# AtoVproject_16n_V1_1.net
KiCad netlist of a schematic drawn in EAGLE
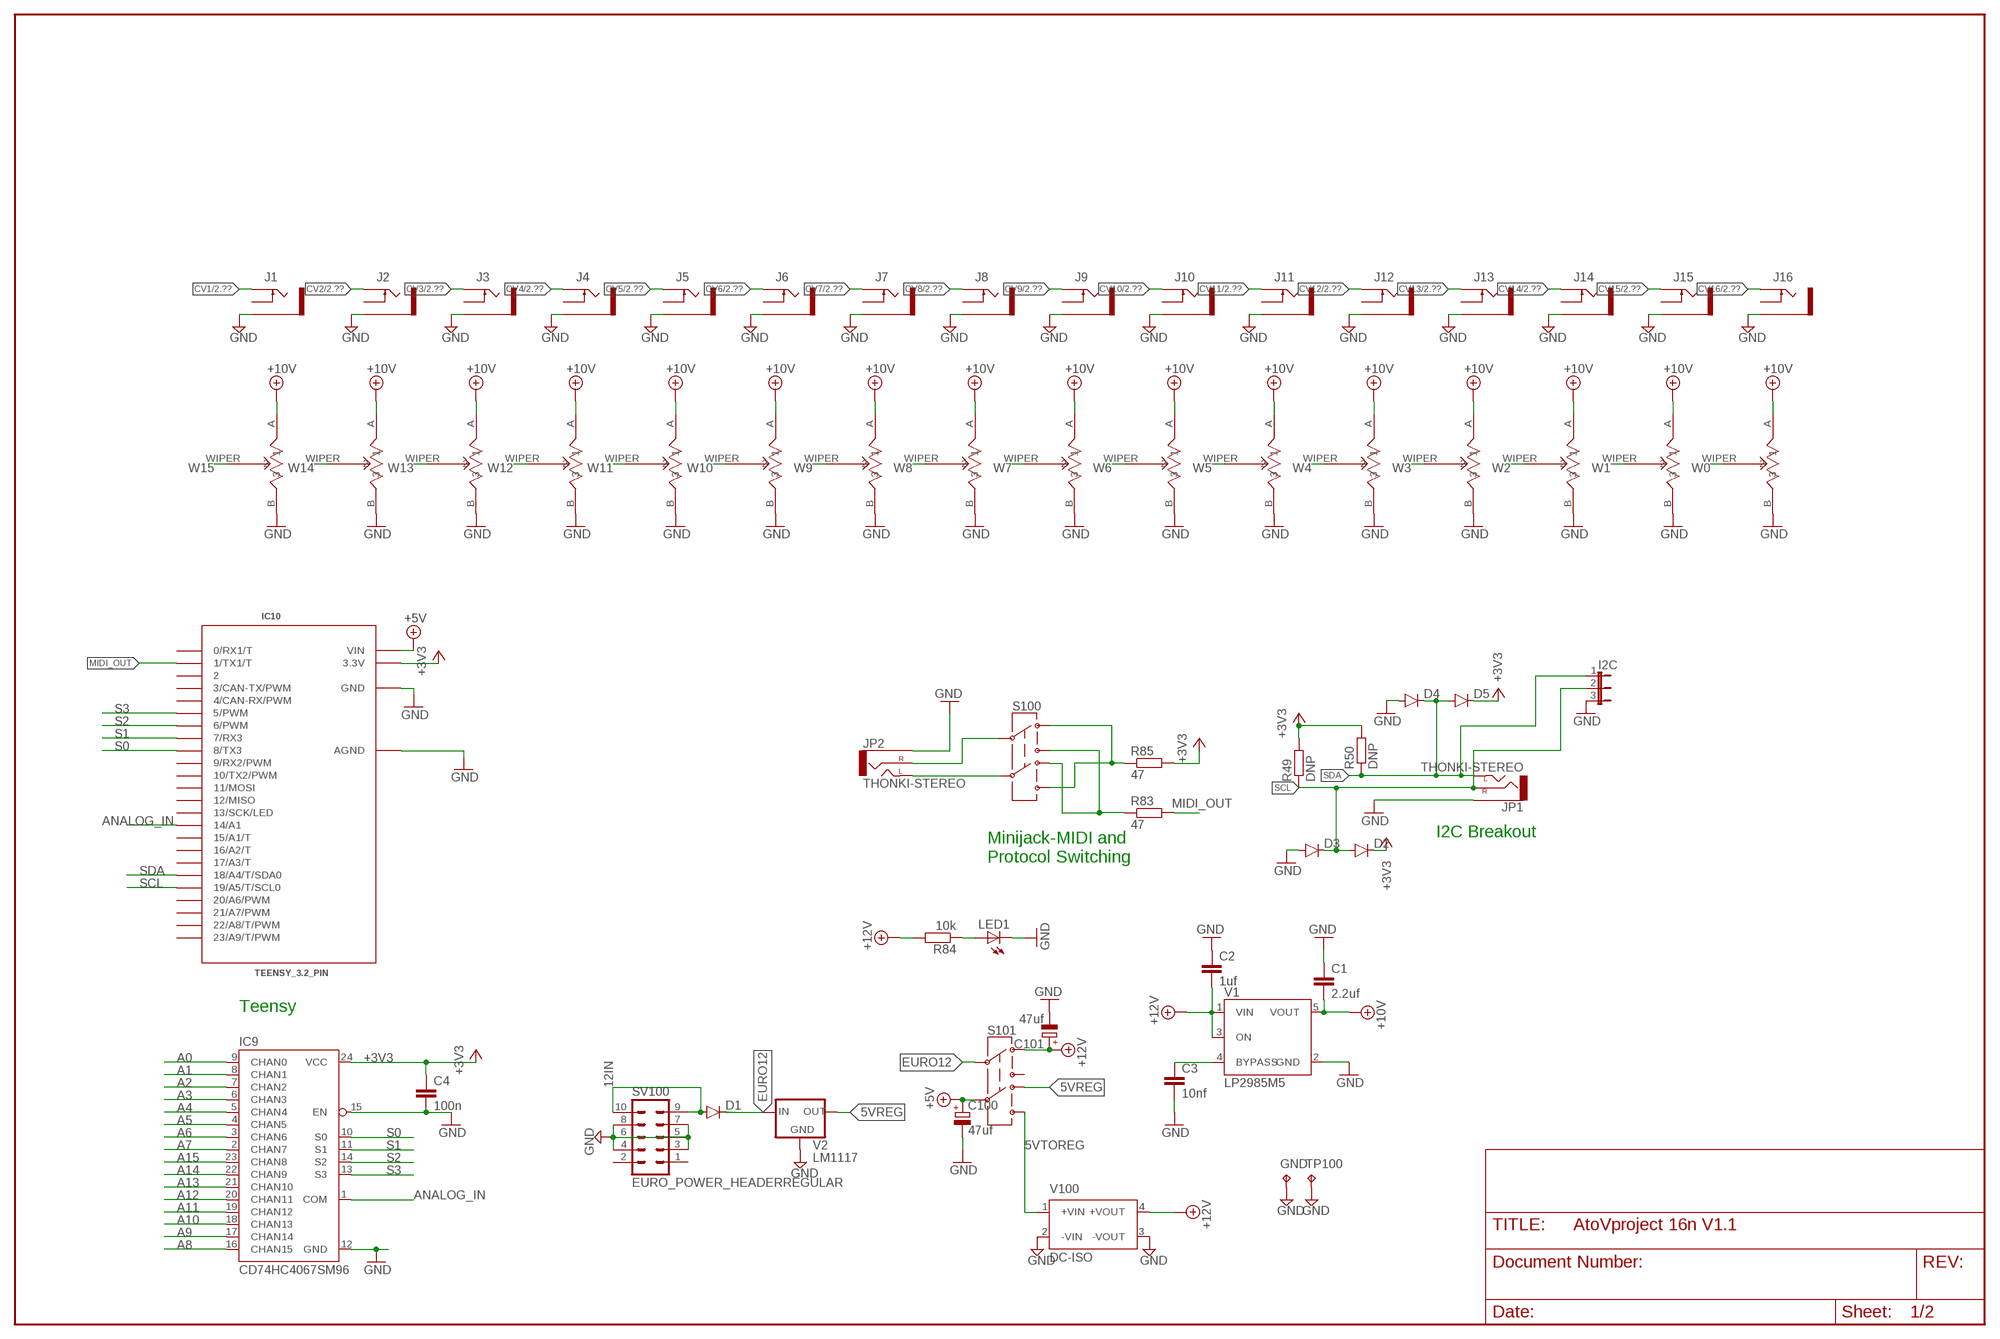
[diagram p0: schematic, sheet 1]
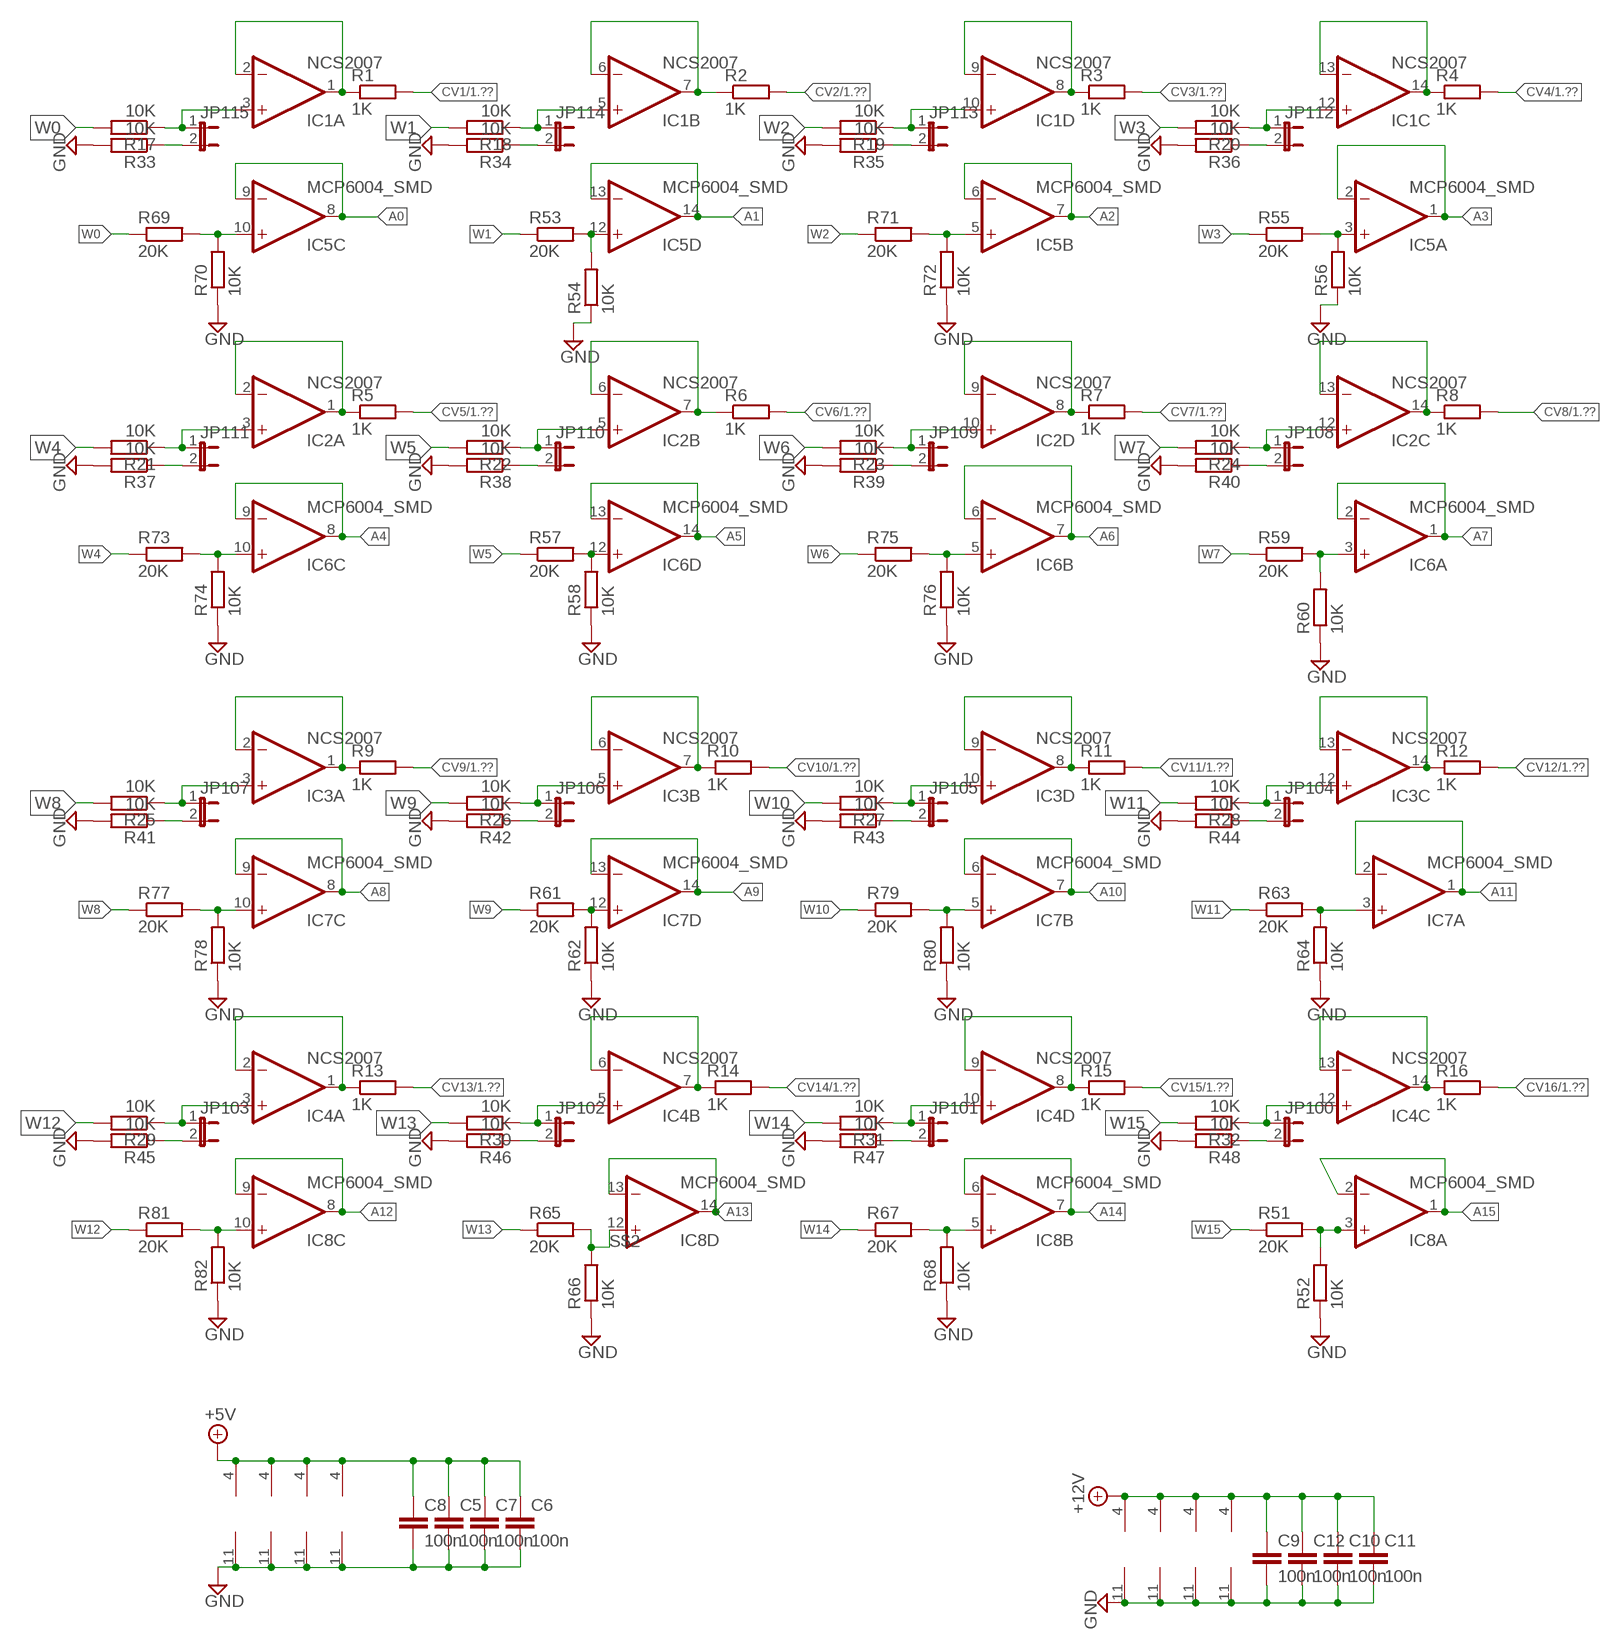
[diagram p1: schematic, sheet 2]

(export (version "E")
  (design (tool "Eeschema 10.0.6"))
  (components
    (comp (ref "C5")
      (value "100n")
      (footprint "eagle-import:C0805")
      (libsource (lib "eagle-import") (part "C-EUC0805"))
    )
    (comp (ref "C6")
      (value "100n")
      (footprint "eagle-import:C0805")
      (libsource (lib "eagle-import") (part "C-EUC0805"))
    )
    (comp (ref "C7")
      (value "100n")
      (footprint "eagle-import:C0805")
      (libsource (lib "eagle-import") (part "C-EUC0805"))
    )
    (comp (ref "C8")
      (value "100n")
      (footprint "eagle-import:C0805")
      (libsource (lib "eagle-import") (part "C-EUC0805"))
    )
    (comp (ref "C9")
      (value "100n")
      (footprint "eagle-import:C0805")
      (libsource (lib "eagle-import") (part "C-EUC0805"))
    )
    (comp (ref "C10")
      (value "100n")
      (footprint "eagle-import:C0805")
      (libsource (lib "eagle-import") (part "C-EUC0805"))
    )
    (comp (ref "C11")
      (value "100n")
      (footprint "eagle-import:C0805")
      (libsource (lib "eagle-import") (part "C-EUC0805"))
    )
    (comp (ref "C12")
      (value "100n")
      (footprint "eagle-import:C0805")
      (libsource (lib "eagle-import") (part "C-EUC0805"))
    )
    (comp (ref "IC1")
      (value "NCS2007")
      (footprint "eagle-import:SO14")
      (libsource (lib "eagle-import") (part "TL074"))
    )
    (comp (ref "IC2")
      (value "NCS2007")
      (footprint "eagle-import:SO14")
      (libsource (lib "eagle-import") (part "TL074"))
    )
    (comp (ref "IC3")
      (value "NCS2007")
      (footprint "eagle-import:SO14")
      (libsource (lib "eagle-import") (part "TL074"))
    )
    (comp (ref "IC4")
      (value "NCS2007")
      (footprint "eagle-import:SO14")
      (libsource (lib "eagle-import") (part "TL074"))
    )
    (comp (ref "IC5")
      (value "MCP6004_SMD")
      (footprint "eagle-import:SO14")
      (libsource (lib "eagle-import") (part "MCP6004_SMD"))
    )
    (comp (ref "IC6")
      (value "MCP6004_SMD")
      (footprint "eagle-import:SO14")
      (libsource (lib "eagle-import") (part "MCP6004_SMD"))
    )
    (comp (ref "IC7")
      (value "MCP6004_SMD")
      (footprint "eagle-import:SO14")
      (libsource (lib "eagle-import") (part "MCP6004_SMD"))
    )
    (comp (ref "IC8")
      (value "MCP6004_SMD")
      (footprint "eagle-import:SO14")
      (libsource (lib "eagle-import") (part "MCP6004_SMD"))
    )
    (comp (ref "JP100")
      (value "JP1E3D")
      (footprint "eagle-import:1X02")
      (libsource (lib "eagle-import") (part "JP1E3D"))
    )
    (comp (ref "JP101")
      (value "JP1E3D")
      (footprint "eagle-import:1X02")
      (libsource (lib "eagle-import") (part "JP1E3D"))
    )
    (comp (ref "JP102")
      (value "JP1E3D")
      (footprint "eagle-import:1X02")
      (libsource (lib "eagle-import") (part "JP1E3D"))
    )
    (comp (ref "JP103")
      (value "JP1E3D")
      (footprint "eagle-import:1X02")
      (libsource (lib "eagle-import") (part "JP1E3D"))
    )
    (comp (ref "JP104")
      (value "JP1E3D")
      (footprint "eagle-import:1X02")
      (libsource (lib "eagle-import") (part "JP1E3D"))
    )
    (comp (ref "JP105")
      (value "JP1E3D")
      (footprint "eagle-import:1X02")
      (libsource (lib "eagle-import") (part "JP1E3D"))
    )
    (comp (ref "JP106")
      (value "JP1E3D")
      (footprint "eagle-import:1X02")
      (libsource (lib "eagle-import") (part "JP1E3D"))
    )
    (comp (ref "JP107")
      (value "JP1E3D")
      (footprint "eagle-import:1X02")
      (libsource (lib "eagle-import") (part "JP1E3D"))
    )
    (comp (ref "JP108")
      (value "JP1E3D")
      (footprint "eagle-import:1X02")
      (libsource (lib "eagle-import") (part "JP1E3D"))
    )
    (comp (ref "JP109")
      (value "JP1E3D")
      (footprint "eagle-import:1X02")
      (libsource (lib "eagle-import") (part "JP1E3D"))
    )
    (comp (ref "JP110")
      (value "JP1E3D")
      (footprint "eagle-import:1X02")
      (libsource (lib "eagle-import") (part "JP1E3D"))
    )
    (comp (ref "JP111")
      (value "JP1E3D")
      (footprint "eagle-import:1X02")
      (libsource (lib "eagle-import") (part "JP1E3D"))
    )
    (comp (ref "JP112")
      (value "JP1E3D")
      (footprint "eagle-import:1X02")
      (libsource (lib "eagle-import") (part "JP1E3D"))
    )
    (comp (ref "JP113")
      (value "JP1E3D")
      (footprint "eagle-import:1X02")
      (libsource (lib "eagle-import") (part "JP1E3D"))
    )
    (comp (ref "JP114")
      (value "JP1E3D")
      (footprint "eagle-import:1X02")
      (libsource (lib "eagle-import") (part "JP1E3D"))
    )
    (comp (ref "JP115")
      (value "JP1E3D")
      (footprint "eagle-import:1X02")
      (libsource (lib "eagle-import") (part "JP1E3D"))
    )
    (comp (ref "R1")
      (value "1K")
      (footprint "eagle-import:R0805")
      (libsource (lib "eagle-import") (part "R-EU_R0805"))
    )
    (comp (ref "R2")
      (value "1K")
      (footprint "eagle-import:R0805")
      (libsource (lib "eagle-import") (part "R-EU_R0805"))
    )
    (comp (ref "R3")
      (value "1K")
      (footprint "eagle-import:R0805")
      (libsource (lib "eagle-import") (part "R-EU_R0805"))
    )
    (comp (ref "R4")
      (value "1K")
      (footprint "eagle-import:R0805")
      (libsource (lib "eagle-import") (part "R-EU_R0805"))
    )
    (comp (ref "R5")
      (value "1K")
      (footprint "eagle-import:R0805")
      (libsource (lib "eagle-import") (part "R-EU_R0805"))
    )
    (comp (ref "R6")
      (value "1K")
      (footprint "eagle-import:R0805")
      (libsource (lib "eagle-import") (part "R-EU_R0805"))
    )
    (comp (ref "R7")
      (value "1K")
      (footprint "eagle-import:R0805")
      (libsource (lib "eagle-import") (part "R-EU_R0805"))
    )
    (comp (ref "R8")
      (value "1K")
      (footprint "eagle-import:R0805")
      (libsource (lib "eagle-import") (part "R-EU_R0805"))
    )
    (comp (ref "R9")
      (value "1K")
      (footprint "eagle-import:R0805")
      (libsource (lib "eagle-import") (part "R-EU_R0805"))
    )
    (comp (ref "R10")
      (value "1K")
      (footprint "eagle-import:R0805")
      (libsource (lib "eagle-import") (part "R-EU_R0805"))
    )
    (comp (ref "R11")
      (value "1K")
      (footprint "eagle-import:R0805")
      (libsource (lib "eagle-import") (part "R-EU_R0805"))
    )
    (comp (ref "R12")
      (value "1K")
      (footprint "eagle-import:R0805")
      (libsource (lib "eagle-import") (part "R-EU_R0805"))
    )
    (comp (ref "R13")
      (value "1K")
      (footprint "eagle-import:R0805")
      (libsource (lib "eagle-import") (part "R-EU_R0805"))
    )
    (comp (ref "R14")
      (value "1K")
      (footprint "eagle-import:R0805")
      (libsource (lib "eagle-import") (part "R-EU_R0805"))
    )
    (comp (ref "R15")
      (value "1K")
      (footprint "eagle-import:R0805")
      (libsource (lib "eagle-import") (part "R-EU_R0805"))
    )
    (comp (ref "R16")
      (value "1K")
      (footprint "eagle-import:R0805")
      (libsource (lib "eagle-import") (part "R-EU_R0805"))
    )
    (comp (ref "R17")
      (value "10K")
      (footprint "eagle-import:R0805")
      (libsource (lib "eagle-import") (part "R-EU_R0805"))
    )
    (comp (ref "R18")
      (value "10K")
      (footprint "eagle-import:R0805")
      (libsource (lib "eagle-import") (part "R-EU_R0805"))
    )
    (comp (ref "R19")
      (value "10K")
      (footprint "eagle-import:R0805")
      (libsource (lib "eagle-import") (part "R-EU_R0805"))
    )
    (comp (ref "R20")
      (value "10K")
      (footprint "eagle-import:R0805")
      (libsource (lib "eagle-import") (part "R-EU_R0805"))
    )
    (comp (ref "R21")
      (value "10K")
      (footprint "eagle-import:R0805")
      (libsource (lib "eagle-import") (part "R-EU_R0805"))
    )
    (comp (ref "R22")
      (value "10K")
      (footprint "eagle-import:R0805")
      (libsource (lib "eagle-import") (part "R-EU_R0805"))
    )
    (comp (ref "R23")
      (value "10K")
      (footprint "eagle-import:R0805")
      (libsource (lib "eagle-import") (part "R-EU_R0805"))
    )
    (comp (ref "R24")
      (value "10K")
      (footprint "eagle-import:R0805")
      (libsource (lib "eagle-import") (part "R-EU_R0805"))
    )
    (comp (ref "R25")
      (value "10K")
      (footprint "eagle-import:R0805")
      (libsource (lib "eagle-import") (part "R-EU_R0805"))
    )
    (comp (ref "R26")
      (value "10K")
      (footprint "eagle-import:R0805")
      (libsource (lib "eagle-import") (part "R-EU_R0805"))
    )
    (comp (ref "R27")
      (value "10K")
      (footprint "eagle-import:R0805")
      (libsource (lib "eagle-import") (part "R-EU_R0805"))
    )
    (comp (ref "R28")
      (value "10K")
      (footprint "eagle-import:R0805")
      (libsource (lib "eagle-import") (part "R-EU_R0805"))
    )
    (comp (ref "R29")
      (value "10K")
      (footprint "eagle-import:R0805")
      (libsource (lib "eagle-import") (part "R-EU_R0805"))
    )
    (comp (ref "R30")
      (value "10K")
      (footprint "eagle-import:R0805")
      (libsource (lib "eagle-import") (part "R-EU_R0805"))
    )
    (comp (ref "R31")
      (value "10K")
      (footprint "eagle-import:R0805")
      (libsource (lib "eagle-import") (part "R-EU_R0805"))
    )
    (comp (ref "R32")
      (value "10K")
      (footprint "eagle-import:R0805")
      (libsource (lib "eagle-import") (part "R-EU_R0805"))
    )
    (comp (ref "R33")
      (value "10K")
      (footprint "eagle-import:R0805")
      (libsource (lib "eagle-import") (part "R-EU_R0805"))
    )
    (comp (ref "R34")
      (value "10K")
      (footprint "eagle-import:R0805")
      (libsource (lib "eagle-import") (part "R-EU_R0805"))
    )
    (comp (ref "R35")
      (value "10K")
      (footprint "eagle-import:R0805")
      (libsource (lib "eagle-import") (part "R-EU_R0805"))
    )
    (comp (ref "R36")
      (value "10K")
      (footprint "eagle-import:R0805")
      (libsource (lib "eagle-import") (part "R-EU_R0805"))
    )
    (comp (ref "R37")
      (value "10K")
      (footprint "eagle-import:R0805")
      (libsource (lib "eagle-import") (part "R-EU_R0805"))
    )
    (comp (ref "R38")
      (value "10K")
      (footprint "eagle-import:R0805")
      (libsource (lib "eagle-import") (part "R-EU_R0805"))
    )
    (comp (ref "R39")
      (value "10K")
      (footprint "eagle-import:R0805")
      (libsource (lib "eagle-import") (part "R-EU_R0805"))
    )
    (comp (ref "R40")
      (value "10K")
      (footprint "eagle-import:R0805")
      (libsource (lib "eagle-import") (part "R-EU_R0805"))
    )
    (comp (ref "R41")
      (value "10K")
      (footprint "eagle-import:R0805")
      (libsource (lib "eagle-import") (part "R-EU_R0805"))
    )
    (comp (ref "R42")
      (value "10K")
      (footprint "eagle-import:R0805")
      (libsource (lib "eagle-import") (part "R-EU_R0805"))
    )
    (comp (ref "R43")
      (value "10K")
      (footprint "eagle-import:R0805")
      (libsource (lib "eagle-import") (part "R-EU_R0805"))
    )
    (comp (ref "R44")
      (value "10K")
      (footprint "eagle-import:R0805")
      (libsource (lib "eagle-import") (part "R-EU_R0805"))
    )
    (comp (ref "R45")
      (value "10K")
      (footprint "eagle-import:R0805")
      (libsource (lib "eagle-import") (part "R-EU_R0805"))
    )
    (comp (ref "R46")
      (value "10K")
      (footprint "eagle-import:R0805")
      (libsource (lib "eagle-import") (part "R-EU_R0805"))
    )
    (comp (ref "R47")
      (value "10K")
      (footprint "eagle-import:R0805")
      (libsource (lib "eagle-import") (part "R-EU_R0805"))
    )
    (comp (ref "R48")
      (value "10K")
      (footprint "eagle-import:R0805")
      (libsource (lib "eagle-import") (part "R-EU_R0805"))
    )
    (comp (ref "R51")
      (value "20K")
      (footprint "eagle-import:R0805")
      (libsource (lib "eagle-import") (part "R-EU_R0805"))
    )
    (comp (ref "R52")
      (value "10K")
      (footprint "eagle-import:R0805")
      (libsource (lib "eagle-import") (part "R-EU_R0805"))
    )
    (comp (ref "R53")
      (value "20K")
      (footprint "eagle-import:R0805")
      (libsource (lib "eagle-import") (part "R-EU_R0805"))
    )
    (comp (ref "R54")
      (value "10K")
      (footprint "eagle-import:R0805")
      (libsource (lib "eagle-import") (part "R-EU_R0805"))
    )
    (comp (ref "R55")
      (value "20K")
      (footprint "eagle-import:R0805")
      (libsource (lib "eagle-import") (part "R-EU_R0805"))
    )
    (comp (ref "R56")
      (value "10K")
      (footprint "eagle-import:R0805")
      (libsource (lib "eagle-import") (part "R-EU_R0805"))
    )
    (comp (ref "R57")
      (value "20K")
      (footprint "eagle-import:R0805")
      (libsource (lib "eagle-import") (part "R-EU_R0805"))
    )
    (comp (ref "R58")
      (value "10K")
      (footprint "eagle-import:R0805")
      (libsource (lib "eagle-import") (part "R-EU_R0805"))
    )
    (comp (ref "R59")
      (value "20K")
      (footprint "eagle-import:R0805")
      (libsource (lib "eagle-import") (part "R-EU_R0805"))
    )
    (comp (ref "R60")
      (value "10K")
      (footprint "eagle-import:R0805")
      (libsource (lib "eagle-import") (part "R-EU_R0805"))
    )
    (comp (ref "R61")
      (value "20K")
      (footprint "eagle-import:R0805")
      (libsource (lib "eagle-import") (part "R-EU_R0805"))
    )
    (comp (ref "R62")
      (value "10K")
      (footprint "eagle-import:R0805")
      (libsource (lib "eagle-import") (part "R-EU_R0805"))
    )
    (comp (ref "R63")
      (value "20K")
      (footprint "eagle-import:R0805")
      (libsource (lib "eagle-import") (part "R-EU_R0805"))
    )
    (comp (ref "R64")
      (value "10K")
      (footprint "eagle-import:R0805")
      (libsource (lib "eagle-import") (part "R-EU_R0805"))
    )
    (comp (ref "R65")
      (value "20K")
      (footprint "eagle-import:R0805")
      (libsource (lib "eagle-import") (part "R-EU_R0805"))
    )
    (comp (ref "R66")
      (value "10K")
      (footprint "eagle-import:R0805")
      (libsource (lib "eagle-import") (part "R-EU_R0805"))
    )
    (comp (ref "R67")
      (value "20K")
      (footprint "eagle-import:R0805")
      (libsource (lib "eagle-import") (part "R-EU_R0805"))
    )
    (comp (ref "R68")
      (value "10K")
      (footprint "eagle-import:R0805")
      (libsource (lib "eagle-import") (part "R-EU_R0805"))
    )
    (comp (ref "R69")
      (value "20K")
      (footprint "eagle-import:R0805")
      (libsource (lib "eagle-import") (part "R-EU_R0805"))
    )
    (comp (ref "R70")
      (value "10K")
      (footprint "eagle-import:R0805")
      (libsource (lib "eagle-import") (part "R-EU_R0805"))
    )
    (comp (ref "R71")
      (value "20K")
      (footprint "eagle-import:R0805")
      (libsource (lib "eagle-import") (part "R-EU_R0805"))
    )
    (comp (ref "R72")
      (value "10K")
      (footprint "eagle-import:R0805")
      (libsource (lib "eagle-import") (part "R-EU_R0805"))
    )
    (comp (ref "R73")
      (value "20K")
      (footprint "eagle-import:R0805")
      (libsource (lib "eagle-import") (part "R-EU_R0805"))
    )
    (comp (ref "R74")
      (value "10K")
      (footprint "eagle-import:R0805")
      (libsource (lib "eagle-import") (part "R-EU_R0805"))
    )
    (comp (ref "R75")
      (value "20K")
      (footprint "eagle-import:R0805")
      (libsource (lib "eagle-import") (part "R-EU_R0805"))
    )
    (comp (ref "R76")
      (value "10K")
      (footprint "eagle-import:R0805")
      (libsource (lib "eagle-import") (part "R-EU_R0805"))
    )
    (comp (ref "R77")
      (value "20K")
      (footprint "eagle-import:R0805")
      (libsource (lib "eagle-import") (part "R-EU_R0805"))
    )
    (comp (ref "R78")
      (value "10K")
      (footprint "eagle-import:R0805")
      (libsource (lib "eagle-import") (part "R-EU_R0805"))
    )
    (comp (ref "R79")
      (value "20K")
      (footprint "eagle-import:R0805")
      (libsource (lib "eagle-import") (part "R-EU_R0805"))
    )
    (comp (ref "R80")
      (value "10K")
      (footprint "eagle-import:R0805")
      (libsource (lib "eagle-import") (part "R-EU_R0805"))
    )
    (comp (ref "R81")
      (value "20K")
      (footprint "eagle-import:R0805")
      (libsource (lib "eagle-import") (part "R-EU_R0805"))
    )
    (comp (ref "R82")
      (value "10K")
      (footprint "eagle-import:R0805")
      (libsource (lib "eagle-import") (part "R-EU_R0805"))
    )
    (comp (ref "C1")
      (value "2.2uf")
      (footprint "eagle-import:C0805")
      (libsource (lib "eagle-import") (part "C-EUC0805"))
    )
    (comp (ref "C2")
      (value "1uf")
      (footprint "eagle-import:C0805")
      (libsource (lib "eagle-import") (part "C-EUC0805"))
    )
    (comp (ref "C3")
      (value "10nf")
      (footprint "eagle-import:C0805")
      (libsource (lib "eagle-import") (part "C-EUC0805"))
    )
    (comp (ref "C4")
      (value "100n")
      (footprint "eagle-import:C0805")
      (libsource (lib "eagle-import") (part "C-EUC0805"))
    )
    (comp (ref "C100")
      (value "47uf")
      (footprint "eagle-import:E2,5-6")
      (libsource (lib "eagle-import") (part "CPOL-EUE2.5-6"))
    )
    (comp (ref "C101")
      (value "47uf")
      (footprint "eagle-import:E2,5-6")
      (libsource (lib "eagle-import") (part "CPOL-EUE2.5-6"))
    )
    (comp (ref "D1")
      (value "DIODE-SOD123")
      (footprint "eagle-import:SOD123")
      (libsource (lib "eagle-import") (part "DIODE-SOD123"))
    )
    (comp (ref "D2")
      (value "DIODESOD123")
      (footprint "eagle-import:SOD-123")
      (libsource (lib "eagle-import") (part "DIODESOD123"))
    )
    (comp (ref "D3")
      (value "DIODESOD123")
      (footprint "eagle-import:SOD-123")
      (libsource (lib "eagle-import") (part "DIODESOD123"))
    )
    (comp (ref "D4")
      (value "DIODESOD123")
      (footprint "eagle-import:SOD-123")
      (libsource (lib "eagle-import") (part "DIODESOD123"))
    )
    (comp (ref "D5")
      (value "DIODESOD123")
      (footprint "eagle-import:SOD-123")
      (libsource (lib "eagle-import") (part "DIODESOD123"))
    )
    (comp (ref "GND")
      (value "TPPAD1-17")
      (footprint "eagle-import:P1-17")
      (libsource (lib "eagle-import") (part "TPPAD1-17"))
    )
    (comp (ref "I2C")
      (value "JP2E")
      (footprint "eagle-import:JP2")
      (libsource (lib "eagle-import") (part "JP2E"))
    )
    (comp (ref "IC9")
      (value "CD74HC4067SM96")
      (footprint "eagle-import:SOIC127P1030X265-24")
      (libsource (lib "eagle-import") (part "744067SO24"))
    )
    (comp (ref "IC10")
      (value "TEENSY_3.2_PIN")
      (footprint "eagle-import:TEENSY_3_AND_LC_SERIES_BOARDS_V1.4_TEENSY_3.0-3.2&LC_DIL")
      (libsource (lib "eagle-import") (part "TEENSY_3.2_PIN"))
    )
    (comp (ref "J1")
      (value "THONKICONN")
      (footprint "eagle-import:WQP-PJ301M-12JACK-BANANA")
      (libsource (lib "eagle-import") (part "THONKICONN"))
    )
    (comp (ref "J2")
      (value "THONKICONN")
      (footprint "eagle-import:WQP-PJ301M-12JACK-BANANA")
      (libsource (lib "eagle-import") (part "THONKICONN"))
    )
    (comp (ref "J3")
      (value "THONKICONN")
      (footprint "eagle-import:WQP-PJ301M-12JACK-BANANA")
      (libsource (lib "eagle-import") (part "THONKICONN"))
    )
    (comp (ref "J4")
      (value "THONKICONN")
      (footprint "eagle-import:WQP-PJ301M-12JACK-BANANA")
      (libsource (lib "eagle-import") (part "THONKICONN"))
    )
    (comp (ref "J5")
      (value "THONKICONN")
      (footprint "eagle-import:WQP-PJ301M-12JACK-BANANA")
      (libsource (lib "eagle-import") (part "THONKICONN"))
    )
    (comp (ref "J6")
      (value "THONKICONN")
      (footprint "eagle-import:WQP-PJ301M-12JACK-BANANA")
      (libsource (lib "eagle-import") (part "THONKICONN"))
    )
    (comp (ref "J7")
      (value "THONKICONN")
      (footprint "eagle-import:WQP-PJ301M-12JACK-BANANA")
      (libsource (lib "eagle-import") (part "THONKICONN"))
    )
    (comp (ref "J8")
      (value "THONKICONN")
      (footprint "eagle-import:WQP-PJ301M-12JACK-BANANA")
      (libsource (lib "eagle-import") (part "THONKICONN"))
    )
    (comp (ref "J9")
      (value "THONKICONN")
      (footprint "eagle-import:WQP-PJ301M-12JACK-BANANA")
      (libsource (lib "eagle-import") (part "THONKICONN"))
    )
    (comp (ref "J10")
      (value "THONKICONN")
      (footprint "eagle-import:WQP-PJ301M-12JACK-BANANA")
      (libsource (lib "eagle-import") (part "THONKICONN"))
    )
    (comp (ref "J11")
      (value "THONKICONN")
      (footprint "eagle-import:WQP-PJ301M-12JACK-BANANA")
      (libsource (lib "eagle-import") (part "THONKICONN"))
    )
    (comp (ref "J12")
      (value "THONKICONN")
      (footprint "eagle-import:WQP-PJ301M-12JACK-BANANA")
      (libsource (lib "eagle-import") (part "THONKICONN"))
    )
    (comp (ref "J13")
      (value "THONKICONN")
      (footprint "eagle-import:WQP-PJ301M-12JACK-BANANA")
      (libsource (lib "eagle-import") (part "THONKICONN"))
    )
    (comp (ref "J14")
      (value "THONKICONN")
      (footprint "eagle-import:WQP-PJ301M-12JACK-BANANA")
      (libsource (lib "eagle-import") (part "THONKICONN"))
    )
    (comp (ref "J15")
      (value "THONKICONN")
      (footprint "eagle-import:WQP-PJ301M-12JACK-BANANA")
      (libsource (lib "eagle-import") (part "THONKICONN"))
    )
    (comp (ref "J16")
      (value "THONKICONN")
      (footprint "eagle-import:WQP-PJ301M-12JACK-BANANA")
      (libsource (lib "eagle-import") (part "THONKICONN"))
    )
    (comp (ref "JP1")
      (value "THONKI-STEREO")
      (footprint "eagle-import:WQP-PJ366ST_JACK")
      (libsource (lib "eagle-import") (part "THONKI-STEREO"))
    )
    (comp (ref "JP2")
      (value "THONKI-STEREO")
      (footprint "eagle-import:WQP-PJ366ST_JACK")
      (libsource (lib "eagle-import") (part "THONKI-STEREO"))
    )
    (comp (ref "LED1")
      (value "LED")
      (footprint "eagle-import:LED3MM")
      (libsource (lib "eagle-import") (part "LED"))
    )
    (comp (ref "R49")
      (value "DNP")
      (footprint "eagle-import:R0805")
      (libsource (lib "eagle-import") (part "R-EU_R0805"))
    )
    (comp (ref "R50")
      (value "DNP")
      (footprint "eagle-import:R0805")
      (libsource (lib "eagle-import") (part "R-EU_R0805"))
    )
    (comp (ref "R83")
      (value "47")
      (footprint "eagle-import:R0805")
      (libsource (lib "eagle-import") (part "R-EU_R0805"))
    )
    (comp (ref "R84")
      (value "10k")
      (footprint "eagle-import:R0805")
      (libsource (lib "eagle-import") (part "R-EU_R0805"))
    )
    (comp (ref "R85")
      (value "47")
      (footprint "eagle-import:R0805")
      (libsource (lib "eagle-import") (part "R-EU_R0805"))
    )
    (comp (ref "S100")
      (value "SWITCH-DPDTEG2211")
      (footprint "eagle-import:EG2211")
      (libsource (lib "eagle-import") (part "SWITCH-DPDTEG2211"))
    )
    (comp (ref "S101")
      (value "SWITCH-DPDTEG2211")
      (footprint "eagle-import:EG2211")
      (libsource (lib "eagle-import") (part "SWITCH-DPDTEG2211"))
    )
    (comp (ref "SV100")
      (value "EURO_POWER_HEADERREGULAR")
      (footprint "eagle-import:EURO_POWER_HEADER")
      (libsource (lib "eagle-import") (part "EURO_POWER_HEADERREGULAR"))
    )
    (comp (ref "TP100")
      (value "TPPAD1-17")
      (footprint "eagle-import:P1-17")
      (libsource (lib "eagle-import") (part "TPPAD1-17"))
    )
    (comp (ref "U$1")
      (value "SLIDERSBOURNS-60MM")
      (footprint "eagle-import:SLIDEPOT-75")
      (libsource (lib "eagle-import") (part "SLIDERSBOURNS-60MM"))
    )
    (comp (ref "U$2")
      (value "SLIDERSBOURNS-60MM")
      (footprint "eagle-import:SLIDEPOT-75")
      (libsource (lib "eagle-import") (part "SLIDERSBOURNS-60MM"))
    )
    (comp (ref "U$3")
      (value "SLIDERSBOURNS-60MM")
      (footprint "eagle-import:SLIDEPOT-75")
      (libsource (lib "eagle-import") (part "SLIDERSBOURNS-60MM"))
    )
    (comp (ref "U$4")
      (value "SLIDERSBOURNS-60MM")
      (footprint "eagle-import:SLIDEPOT-75")
      (libsource (lib "eagle-import") (part "SLIDERSBOURNS-60MM"))
    )
    (comp (ref "U$5")
      (value "SLIDERSBOURNS-60MM")
      (footprint "eagle-import:SLIDEPOT-75")
      (libsource (lib "eagle-import") (part "SLIDERSBOURNS-60MM"))
    )
    (comp (ref "U$6")
      (value "SLIDERSBOURNS-60MM")
      (footprint "eagle-import:SLIDEPOT-75")
      (libsource (lib "eagle-import") (part "SLIDERSBOURNS-60MM"))
    )
    (comp (ref "U$7")
      (value "SLIDERSBOURNS-60MM")
      (footprint "eagle-import:SLIDEPOT-75")
      (libsource (lib "eagle-import") (part "SLIDERSBOURNS-60MM"))
    )
    (comp (ref "U$8")
      (value "SLIDERSBOURNS-60MM")
      (footprint "eagle-import:SLIDEPOT-75")
      (libsource (lib "eagle-import") (part "SLIDERSBOURNS-60MM"))
    )
    (comp (ref "U$9")
      (value "SLIDERSBOURNS-60MM")
      (footprint "eagle-import:SLIDEPOT-75")
      (libsource (lib "eagle-import") (part "SLIDERSBOURNS-60MM"))
    )
    (comp (ref "U$10")
      (value "SLIDERSBOURNS-60MM")
      (footprint "eagle-import:SLIDEPOT-75")
      (libsource (lib "eagle-import") (part "SLIDERSBOURNS-60MM"))
    )
    (comp (ref "U$11")
      (value "SLIDERSBOURNS-60MM")
      (footprint "eagle-import:SLIDEPOT-75")
      (libsource (lib "eagle-import") (part "SLIDERSBOURNS-60MM"))
    )
    (comp (ref "U$12")
      (value "SLIDERSBOURNS-60MM")
      (footprint "eagle-import:SLIDEPOT-75")
      (libsource (lib "eagle-import") (part "SLIDERSBOURNS-60MM"))
    )
    (comp (ref "U$13")
      (value "SLIDERSBOURNS-60MM")
      (footprint "eagle-import:SLIDEPOT-75")
      (libsource (lib "eagle-import") (part "SLIDERSBOURNS-60MM"))
    )
    (comp (ref "U$14")
      (value "SLIDERSBOURNS-60MM")
      (footprint "eagle-import:SLIDEPOT-75")
      (libsource (lib "eagle-import") (part "SLIDERSBOURNS-60MM"))
    )
    (comp (ref "U$15")
      (value "SLIDERSBOURNS-60MM")
      (footprint "eagle-import:SLIDEPOT-75")
      (libsource (lib "eagle-import") (part "SLIDERSBOURNS-60MM"))
    )
    (comp (ref "U$16")
      (value "SLIDERSBOURNS-60MM")
      (footprint "eagle-import:SLIDEPOT-75")
      (libsource (lib "eagle-import") (part "SLIDERSBOURNS-60MM"))
    )
    (comp (ref "V1")
      (value "LP2985M5")
      (footprint "eagle-import:SOT23-5")
      (libsource (lib "eagle-import") (part "LP2985M5"))
    )
    (comp (ref "V2")
      (value "LM1117")
      (footprint "eagle-import:SOT223")
      (libsource (lib "eagle-import") (part "LM1117"))
    )
    (comp (ref "V100")
      (value "DC-ISO")
      (footprint "eagle-import:TMA")
      (libsource (lib "eagle-import") (part "DC-ISO"))
    )
  )
  (nets
    (net (code "1") (name "+3V3") (class "Default")
      (node (ref "C4") (pin "1") (pinfunction "1_1") (pintype "passive"))
      (node (ref "D2") (pin "C") (pinfunction "C_C") (pintype "passive"))
      (node (ref "D5") (pin "C") (pinfunction "C_C") (pintype "passive"))
      (node (ref "IC10") (pin "3.3V") (pinfunction "3.3V_3.3V") (pintype "power_in"))
      (node (ref "IC9") (pin "24") (pinfunction "VCC_24") (pintype "bidirectional"))
      (node (ref "R49") (pin "2") (pinfunction "2_2") (pintype "passive"))
      (node (ref "R50") (pin "2") (pinfunction "2_2") (pintype "passive"))
      (node (ref "R85") (pin "2") (pinfunction "2_2") (pintype "passive"))
    )
    (net (code "2") (name "+5V") (class "Default")
      (node (ref "C100") (pin "+") (pinfunction "+_+") (pintype "passive"))
      (node (ref "C5") (pin "1") (pinfunction "1_1") (pintype "passive"))
      (node (ref "C6") (pin "1") (pinfunction "1_1") (pintype "passive"))
      (node (ref "C7") (pin "1") (pinfunction "1_1") (pintype "passive"))
      (node (ref "C8") (pin "1") (pinfunction "1_1") (pintype "passive"))
      (node (ref "IC10") (pin "VIN") (pinfunction "VIN_VIN") (pintype "power_in"))
      (node (ref "IC5") (pin "4") (pinfunction "V+_4") (pintype "power_in"))
      (node (ref "IC6") (pin "4") (pinfunction "V+_4") (pintype "power_in"))
      (node (ref "IC7") (pin "4") (pinfunction "V+_4") (pintype "power_in"))
      (node (ref "IC8") (pin "4") (pinfunction "V+_4") (pintype "power_in"))
      (node (ref "S101") (pin "P2") (pinfunction "5_P2") (pintype "bidirectional"))
    )
    (net (code "3") (name "+10V") (class "Default")
      (node (ref "C1") (pin "2") (pinfunction "2_2") (pintype "passive"))
      (node (ref "U$1") (pin "A") (pinfunction "1_A") (pintype "bidirectional"))
      (node (ref "U$10") (pin "A") (pinfunction "1_A") (pintype "bidirectional"))
      (node (ref "U$11") (pin "A") (pinfunction "1_A") (pintype "bidirectional"))
      (node (ref "U$12") (pin "A") (pinfunction "1_A") (pintype "bidirectional"))
      (node (ref "U$13") (pin "A") (pinfunction "1_A") (pintype "bidirectional"))
      (node (ref "U$14") (pin "A") (pinfunction "1_A") (pintype "bidirectional"))
      (node (ref "U$15") (pin "A") (pinfunction "1_A") (pintype "bidirectional"))
      (node (ref "U$16") (pin "A") (pinfunction "1_A") (pintype "bidirectional"))
      (node (ref "U$2") (pin "A") (pinfunction "1_A") (pintype "bidirectional"))
      (node (ref "U$3") (pin "A") (pinfunction "1_A") (pintype "bidirectional"))
      (node (ref "U$4") (pin "A") (pinfunction "1_A") (pintype "bidirectional"))
      (node (ref "U$5") (pin "A") (pinfunction "1_A") (pintype "bidirectional"))
      (node (ref "U$6") (pin "A") (pinfunction "1_A") (pintype "bidirectional"))
      (node (ref "U$7") (pin "A") (pinfunction "1_A") (pintype "bidirectional"))
      (node (ref "U$8") (pin "A") (pinfunction "1_A") (pintype "bidirectional"))
      (node (ref "U$9") (pin "A") (pinfunction "1_A") (pintype "bidirectional"))
      (node (ref "V1") (pin "5") (pinfunction "VOUT_5") (pintype "output"))
    )
    (net (code "4") (name "+12V") (class "Default")
      (node (ref "C10") (pin "1") (pinfunction "1_1") (pintype "passive"))
      (node (ref "C101") (pin "+") (pinfunction "+_+") (pintype "passive"))
      (node (ref "C11") (pin "1") (pinfunction "1_1") (pintype "passive"))
      (node (ref "C12") (pin "1") (pinfunction "1_1") (pintype "passive"))
      (node (ref "C2") (pin "2") (pinfunction "2_2") (pintype "passive"))
      (node (ref "C9") (pin "1") (pinfunction "1_1") (pintype "passive"))
      (node (ref "IC1") (pin "4") (pinfunction "V+_4") (pintype "power_in"))
      (node (ref "IC2") (pin "4") (pinfunction "V+_4") (pintype "power_in"))
      (node (ref "IC3") (pin "4") (pinfunction "V+_4") (pintype "power_in"))
      (node (ref "IC4") (pin "4") (pinfunction "V+_4") (pintype "power_in"))
      (node (ref "R84") (pin "2") (pinfunction "2_2") (pintype "passive"))
      (node (ref "S101") (pin "P1-TA") (pinfunction "1_P1-TA") (pintype "bidirectional"))
      (node (ref "V1") (pin "1") (pinfunction "VIN_1") (pintype "power_in"))
      (node (ref "V1") (pin "3") (pinfunction "ON_3") (pintype "input"))
      (node (ref "V100") (pin "4") (pinfunction "+VOUT_4") (pintype "passive"))
    )
    (net (code "5") (name "5VREG") (class "Default")
      (node (ref "S101") (pin "P2-TA") (pinfunction "4_P2-TA") (pintype "bidirectional"))
      (node (ref "V2") (pin "OUT") (pinfunction "OUT_OUT") (pintype "passive"))
      (node (ref "V2") (pin "TAB") (pinfunction "OUT_TAB") (pintype "passive"))
    )
    (net (code "6") (name "5VTOREG") (class "Default")
      (node (ref "S101") (pin "P2-TB") (pinfunction "6_P2-TB") (pintype "bidirectional"))
      (node (ref "V100") (pin "1") (pinfunction "+VIN_1") (pintype "passive"))
    )
    (net (code "7") (name "12IN") (class "Default")
      (node (ref "D1") (pin "A") (pinfunction "A_A") (pintype "passive"))
      (node (ref "SV100") (pin "10") (pinfunction "10_10") (pintype "passive"))
      (node (ref "SV100") (pin "9") (pinfunction "9_9") (pintype "passive"))
    )
    (net (code "8") (name "A0") (class "Default")
      (node (ref "IC5") (pin "8") (pinfunction "OUT_8") (pintype "output"))
      (node (ref "IC5") (pin "9") (pinfunction "-IN_9") (pintype "input"))
      (node (ref "IC9") (pin "9") (pinfunction "CHAN0_9") (pintype "bidirectional"))
    )
    (net (code "9") (name "A1") (class "Default")
      (node (ref "IC5") (pin "13") (pinfunction "-IN_13") (pintype "input"))
      (node (ref "IC5") (pin "14") (pinfunction "OUT_14") (pintype "output"))
      (node (ref "IC9") (pin "8") (pinfunction "CHAN1_8") (pintype "bidirectional"))
    )
    (net (code "10") (name "A2") (class "Default")
      (node (ref "IC5") (pin "6") (pinfunction "-IN_6") (pintype "input"))
      (node (ref "IC5") (pin "7") (pinfunction "OUT_7") (pintype "output"))
      (node (ref "IC9") (pin "7") (pinfunction "CHAN2_7") (pintype "bidirectional"))
    )
    (net (code "11") (name "A3") (class "Default")
      (node (ref "IC5") (pin "1") (pinfunction "OUT_1") (pintype "output"))
      (node (ref "IC5") (pin "2") (pinfunction "-IN_2") (pintype "input"))
      (node (ref "IC9") (pin "6") (pinfunction "CHAN3_6") (pintype "bidirectional"))
    )
    (net (code "12") (name "A4") (class "Default")
      (node (ref "IC6") (pin "8") (pinfunction "OUT_8") (pintype "output"))
      (node (ref "IC6") (pin "9") (pinfunction "-IN_9") (pintype "input"))
      (node (ref "IC9") (pin "5") (pinfunction "CHAN4_5") (pintype "bidirectional"))
    )
    (net (code "13") (name "A5") (class "Default")
      (node (ref "IC6") (pin "13") (pinfunction "-IN_13") (pintype "input"))
      (node (ref "IC6") (pin "14") (pinfunction "OUT_14") (pintype "output"))
      (node (ref "IC9") (pin "4") (pinfunction "CHAN5_4") (pintype "bidirectional"))
    )
    (net (code "14") (name "A6") (class "Default")
      (node (ref "IC6") (pin "6") (pinfunction "-IN_6") (pintype "input"))
      (node (ref "IC6") (pin "7") (pinfunction "OUT_7") (pintype "output"))
      (node (ref "IC9") (pin "3") (pinfunction "CHAN6_3") (pintype "bidirectional"))
    )
    (net (code "15") (name "A7") (class "Default")
      (node (ref "IC6") (pin "1") (pinfunction "OUT_1") (pintype "output"))
      (node (ref "IC6") (pin "2") (pinfunction "-IN_2") (pintype "input"))
      (node (ref "IC9") (pin "2") (pinfunction "CHAN7_2") (pintype "bidirectional"))
    )
    (net (code "16") (name "A8") (class "Default")
      (node (ref "IC7") (pin "8") (pinfunction "OUT_8") (pintype "output"))
      (node (ref "IC7") (pin "9") (pinfunction "-IN_9") (pintype "input"))
      (node (ref "IC9") (pin "16") (pinfunction "CHAN15_16") (pintype "bidirectional"))
    )
    (net (code "17") (name "A9") (class "Default")
      (node (ref "IC7") (pin "13") (pinfunction "-IN_13") (pintype "input"))
      (node (ref "IC7") (pin "14") (pinfunction "OUT_14") (pintype "output"))
      (node (ref "IC9") (pin "17") (pinfunction "CHAN14_17") (pintype "bidirectional"))
    )
    (net (code "18") (name "A10") (class "Default")
      (node (ref "IC7") (pin "6") (pinfunction "-IN_6") (pintype "input"))
      (node (ref "IC7") (pin "7") (pinfunction "OUT_7") (pintype "output"))
      (node (ref "IC9") (pin "18") (pinfunction "CHAN13_18") (pintype "bidirectional"))
    )
    (net (code "19") (name "A11") (class "Default")
      (node (ref "IC7") (pin "1") (pinfunction "OUT_1") (pintype "output"))
      (node (ref "IC7") (pin "2") (pinfunction "-IN_2") (pintype "input"))
      (node (ref "IC9") (pin "19") (pinfunction "CHAN12_19") (pintype "bidirectional"))
    )
    (net (code "20") (name "A12") (class "Default")
      (node (ref "IC8") (pin "8") (pinfunction "OUT_8") (pintype "output"))
      (node (ref "IC8") (pin "9") (pinfunction "-IN_9") (pintype "input"))
      (node (ref "IC9") (pin "20") (pinfunction "CHAN11_20") (pintype "bidirectional"))
    )
    (net (code "21") (name "A13") (class "Default")
      (node (ref "IC8") (pin "13") (pinfunction "-IN_13") (pintype "input"))
      (node (ref "IC8") (pin "14") (pinfunction "OUT_14") (pintype "output"))
      (node (ref "IC9") (pin "21") (pinfunction "CHAN10_21") (pintype "bidirectional"))
    )
    (net (code "22") (name "A14") (class "Default")
      (node (ref "IC8") (pin "6") (pinfunction "-IN_6") (pintype "input"))
      (node (ref "IC8") (pin "7") (pinfunction "OUT_7") (pintype "output"))
      (node (ref "IC9") (pin "22") (pinfunction "CHAN9_22") (pintype "bidirectional"))
    )
    (net (code "23") (name "A15") (class "Default")
      (node (ref "IC8") (pin "1") (pinfunction "OUT_1") (pintype "output"))
      (node (ref "IC8") (pin "2") (pinfunction "-IN_2") (pintype "input"))
      (node (ref "IC9") (pin "23") (pinfunction "CHAN8_23") (pintype "bidirectional"))
    )
    (net (code "24") (name "ANALOG_IN") (class "Default")
      (node (ref "IC10") (pin "14/A0") (pinfunction "14/A1_14/A0") (pintype "bidirectional"))
      (node (ref "IC9") (pin "1") (pinfunction "COM_1") (pintype "bidirectional"))
    )
    (net (code "25") (name "CV1") (class "Default")
      (node (ref "J1") (pin "P$1_TIP") (pinfunction "TIP_P$1_TIP") (pintype "passive"))
      (node (ref "R1") (pin "2") (pinfunction "2_2") (pintype "passive"))
    )
    (net (code "26") (name "CV2") (class "Default")
      (node (ref "J2") (pin "P$1_TIP") (pinfunction "TIP_P$1_TIP") (pintype "passive"))
      (node (ref "R2") (pin "2") (pinfunction "2_2") (pintype "passive"))
    )
    (net (code "27") (name "CV3") (class "Default")
      (node (ref "J3") (pin "P$1_TIP") (pinfunction "TIP_P$1_TIP") (pintype "passive"))
      (node (ref "R3") (pin "2") (pinfunction "2_2") (pintype "passive"))
    )
    (net (code "28") (name "CV4") (class "Default")
      (node (ref "J4") (pin "P$1_TIP") (pinfunction "TIP_P$1_TIP") (pintype "passive"))
      (node (ref "R4") (pin "2") (pinfunction "2_2") (pintype "passive"))
    )
    (net (code "29") (name "CV5") (class "Default")
      (node (ref "J5") (pin "P$1_TIP") (pinfunction "TIP_P$1_TIP") (pintype "passive"))
      (node (ref "R5") (pin "2") (pinfunction "2_2") (pintype "passive"))
    )
    (net (code "30") (name "CV6") (class "Default")
      (node (ref "J6") (pin "P$1_TIP") (pinfunction "TIP_P$1_TIP") (pintype "passive"))
      (node (ref "R6") (pin "2") (pinfunction "2_2") (pintype "passive"))
    )
    (net (code "31") (name "CV7") (class "Default")
      (node (ref "J7") (pin "P$1_TIP") (pinfunction "TIP_P$1_TIP") (pintype "passive"))
      (node (ref "R7") (pin "2") (pinfunction "2_2") (pintype "passive"))
    )
    (net (code "32") (name "CV8") (class "Default")
      (node (ref "J8") (pin "P$1_TIP") (pinfunction "TIP_P$1_TIP") (pintype "passive"))
      (node (ref "R8") (pin "2") (pinfunction "2_2") (pintype "passive"))
    )
    (net (code "33") (name "CV9") (class "Default")
      (node (ref "J9") (pin "P$1_TIP") (pinfunction "TIP_P$1_TIP") (pintype "passive"))
      (node (ref "R9") (pin "2") (pinfunction "2_2") (pintype "passive"))
    )
    (net (code "34") (name "CV10") (class "Default")
      (node (ref "J10") (pin "P$1_TIP") (pinfunction "TIP_P$1_TIP") (pintype "passive"))
      (node (ref "R10") (pin "2") (pinfunction "2_2") (pintype "passive"))
    )
    (net (code "35") (name "CV11") (class "Default")
      (node (ref "J11") (pin "P$1_TIP") (pinfunction "TIP_P$1_TIP") (pintype "passive"))
      (node (ref "R11") (pin "2") (pinfunction "2_2") (pintype "passive"))
    )
    (net (code "36") (name "CV12") (class "Default")
      (node (ref "J12") (pin "P$1_TIP") (pinfunction "TIP_P$1_TIP") (pintype "passive"))
      (node (ref "R12") (pin "2") (pinfunction "2_2") (pintype "passive"))
    )
    (net (code "37") (name "CV13") (class "Default")
      (node (ref "J13") (pin "P$1_TIP") (pinfunction "TIP_P$1_TIP") (pintype "passive"))
      (node (ref "R13") (pin "2") (pinfunction "2_2") (pintype "passive"))
    )
    (net (code "38") (name "CV14") (class "Default")
      (node (ref "J14") (pin "P$1_TIP") (pinfunction "TIP_P$1_TIP") (pintype "passive"))
      (node (ref "R14") (pin "2") (pinfunction "2_2") (pintype "passive"))
    )
    (net (code "39") (name "CV15") (class "Default")
      (node (ref "J15") (pin "P$1_TIP") (pinfunction "TIP_P$1_TIP") (pintype "passive"))
      (node (ref "R15") (pin "2") (pinfunction "2_2") (pintype "passive"))
    )
    (net (code "40") (name "CV16") (class "Default")
      (node (ref "J16") (pin "P$1_TIP") (pinfunction "TIP_P$1_TIP") (pintype "passive"))
      (node (ref "R16") (pin "2") (pinfunction "2_2") (pintype "passive"))
    )
    (net (code "41") (name "EURO12") (class "Default")
      (node (ref "D1") (pin "C") (pinfunction "C_C") (pintype "passive"))
      (node (ref "S101") (pin "P1") (pinfunction "2_P1") (pintype "bidirectional"))
      (node (ref "V2") (pin "IN") (pinfunction "IN_IN") (pintype "input"))
    )
    (net (code "42") (name "GND") (class "Default")
      (node (ref "C1") (pin "1") (pinfunction "1_1") (pintype "passive"))
      (node (ref "C10") (pin "2") (pinfunction "2_2") (pintype "passive"))
      (node (ref "C100") (pin "-") (pinfunction "-_-") (pintype "passive"))
      (node (ref "C101") (pin "-") (pinfunction "-_-") (pintype "passive"))
      (node (ref "C11") (pin "2") (pinfunction "2_2") (pintype "passive"))
      (node (ref "C12") (pin "2") (pinfunction "2_2") (pintype "passive"))
      (node (ref "C2") (pin "1") (pinfunction "1_1") (pintype "passive"))
      (node (ref "C3") (pin "2") (pinfunction "2_2") (pintype "passive"))
      (node (ref "C4") (pin "2") (pinfunction "2_2") (pintype "passive"))
      (node (ref "C5") (pin "2") (pinfunction "2_2") (pintype "passive"))
      (node (ref "C6") (pin "2") (pinfunction "2_2") (pintype "passive"))
      (node (ref "C7") (pin "2") (pinfunction "2_2") (pintype "passive"))
      (node (ref "C8") (pin "2") (pinfunction "2_2") (pintype "passive"))
      (node (ref "C9") (pin "2") (pinfunction "2_2") (pintype "passive"))
      (node (ref "D3") (pin "A") (pinfunction "A_A") (pintype "passive"))
      (node (ref "D4") (pin "A") (pinfunction "A_A") (pintype "passive"))
      (node (ref "GND") (pin "TP") (pinfunction "TP_TP") (pintype "input"))
      (node (ref "I2C") (pin "3") (pinfunction "3_3") (pintype "passive"))
      (node (ref "IC1") (pin "11") (pinfunction "V-_11") (pintype "power_in"))
      (node (ref "IC10") (pin "AGND") (pinfunction "AGND_AGND") (pintype "power_in"))
      (node (ref "IC10") (pin "GND") (pinfunction "GND_GND") (pintype "power_in"))
      (node (ref "IC2") (pin "11") (pinfunction "V-_11") (pintype "power_in"))
      (node (ref "IC3") (pin "11") (pinfunction "V-_11") (pintype "power_in"))
      (node (ref "IC4") (pin "11") (pinfunction "V-_11") (pintype "power_in"))
      (node (ref "IC5") (pin "11") (pinfunction "V-_11") (pintype "power_in"))
      (node (ref "IC6") (pin "11") (pinfunction "V-_11") (pintype "power_in"))
      (node (ref "IC7") (pin "11") (pinfunction "V-_11") (pintype "power_in"))
      (node (ref "IC8") (pin "11") (pinfunction "V-_11") (pintype "power_in"))
      (node (ref "IC9") (pin "12") (pinfunction "GND_12") (pintype "bidirectional"))
      (node (ref "IC9") (pin "15") (pinfunction "EN_15") (pintype "input"))
      (node (ref "J1") (pin "P$3_SLEEVE") (pinfunction "SLEEVE_P$3_SLEEVE") (pintype "passive"))
      (node (ref "J10") (pin "P$3_SLEEVE") (pinfunction "SLEEVE_P$3_SLEEVE") (pintype "passive"))
      (node (ref "J11") (pin "P$3_SLEEVE") (pinfunction "SLEEVE_P$3_SLEEVE") (pintype "passive"))
      (node (ref "J12") (pin "P$3_SLEEVE") (pinfunction "SLEEVE_P$3_SLEEVE") (pintype "passive"))
      (node (ref "J13") (pin "P$3_SLEEVE") (pinfunction "SLEEVE_P$3_SLEEVE") (pintype "passive"))
      (node (ref "J14") (pin "P$3_SLEEVE") (pinfunction "SLEEVE_P$3_SLEEVE") (pintype "passive"))
      (node (ref "J15") (pin "P$3_SLEEVE") (pinfunction "SLEEVE_P$3_SLEEVE") (pintype "passive"))
      (node (ref "J16") (pin "P$3_SLEEVE") (pinfunction "SLEEVE_P$3_SLEEVE") (pintype "passive"))
      (node (ref "J2") (pin "P$3_SLEEVE") (pinfunction "SLEEVE_P$3_SLEEVE") (pintype "passive"))
      (node (ref "J3") (pin "P$3_SLEEVE") (pinfunction "SLEEVE_P$3_SLEEVE") (pintype "passive"))
      (node (ref "J4") (pin "P$3_SLEEVE") (pinfunction "SLEEVE_P$3_SLEEVE") (pintype "passive"))
      (node (ref "J5") (pin "P$3_SLEEVE") (pinfunction "SLEEVE_P$3_SLEEVE") (pintype "passive"))
      (node (ref "J6") (pin "P$3_SLEEVE") (pinfunction "SLEEVE_P$3_SLEEVE") (pintype "passive"))
      (node (ref "J7") (pin "P$3_SLEEVE") (pinfunction "SLEEVE_P$3_SLEEVE") (pintype "passive"))
      (node (ref "J8") (pin "P$3_SLEEVE") (pinfunction "SLEEVE_P$3_SLEEVE") (pintype "passive"))
      (node (ref "J9") (pin "P$3_SLEEVE") (pinfunction "SLEEVE_P$3_SLEEVE") (pintype "passive"))
      (node (ref "JP1") (pin "P$3_SLEEVE") (pinfunction "SLEEVE_P$3_SLEEVE") (pintype "bidirectional"))
      (node (ref "JP2") (pin "P$3_SLEEVE") (pinfunction "SLEEVE_P$3_SLEEVE") (pintype "bidirectional"))
      (node (ref "LED1") (pin "K") (pinfunction "C_K") (pintype "passive"))
      (node (ref "R33") (pin "2") (pinfunction "2_2") (pintype "passive"))
      (node (ref "R34") (pin "2") (pinfunction "2_2") (pintype "passive"))
      (node (ref "R35") (pin "2") (pinfunction "2_2") (pintype "passive"))
      (node (ref "R36") (pin "2") (pinfunction "2_2") (pintype "passive"))
      (node (ref "R37") (pin "2") (pinfunction "2_2") (pintype "passive"))
      (node (ref "R38") (pin "2") (pinfunction "2_2") (pintype "passive"))
      (node (ref "R39") (pin "2") (pinfunction "2_2") (pintype "passive"))
      (node (ref "R40") (pin "2") (pinfunction "2_2") (pintype "passive"))
      (node (ref "R41") (pin "2") (pinfunction "2_2") (pintype "passive"))
      (node (ref "R42") (pin "2") (pinfunction "2_2") (pintype "passive"))
      (node (ref "R43") (pin "2") (pinfunction "2_2") (pintype "passive"))
      (node (ref "R44") (pin "2") (pinfunction "2_2") (pintype "passive"))
      (node (ref "R45") (pin "2") (pinfunction "2_2") (pintype "passive"))
      (node (ref "R46") (pin "2") (pinfunction "2_2") (pintype "passive"))
      (node (ref "R47") (pin "2") (pinfunction "2_2") (pintype "passive"))
      (node (ref "R48") (pin "2") (pinfunction "2_2") (pintype "passive"))
      (node (ref "R52") (pin "1") (pinfunction "1_1") (pintype "passive"))
      (node (ref "R54") (pin "1") (pinfunction "1_1") (pintype "passive"))
      (node (ref "R56") (pin "1") (pinfunction "1_1") (pintype "passive"))
      (node (ref "R58") (pin "1") (pinfunction "1_1") (pintype "passive"))
      (node (ref "R60") (pin "1") (pinfunction "1_1") (pintype "passive"))
      (node (ref "R62") (pin "1") (pinfunction "1_1") (pintype "passive"))
      (node (ref "R64") (pin "1") (pinfunction "1_1") (pintype "passive"))
      (node (ref "R66") (pin "1") (pinfunction "1_1") (pintype "passive"))
      (node (ref "R68") (pin "1") (pinfunction "1_1") (pintype "passive"))
      (node (ref "R70") (pin "1") (pinfunction "1_1") (pintype "passive"))
      (node (ref "R72") (pin "1") (pinfunction "1_1") (pintype "passive"))
      (node (ref "R74") (pin "1") (pinfunction "1_1") (pintype "passive"))
      (node (ref "R76") (pin "1") (pinfunction "1_1") (pintype "passive"))
      (node (ref "R78") (pin "1") (pinfunction "1_1") (pintype "passive"))
      (node (ref "R80") (pin "1") (pinfunction "1_1") (pintype "passive"))
      (node (ref "R82") (pin "1") (pinfunction "1_1") (pintype "passive"))
      (node (ref "SV100") (pin "3") (pinfunction "3_3") (pintype "passive"))
      (node (ref "SV100") (pin "4") (pinfunction "4_4") (pintype "passive"))
      (node (ref "SV100") (pin "5") (pinfunction "5_5") (pintype "passive"))
      (node (ref "SV100") (pin "6") (pinfunction "6_6") (pintype "passive"))
      (node (ref "SV100") (pin "7") (pinfunction "7_7") (pintype "passive"))
      (node (ref "SV100") (pin "8") (pinfunction "8_8") (pintype "passive"))
      (node (ref "TP100") (pin "TP") (pinfunction "TP_TP") (pintype "input"))
      (node (ref "U$1") (pin "B") (pinfunction "3_B") (pintype "bidirectional"))
      (node (ref "U$10") (pin "B") (pinfunction "3_B") (pintype "bidirectional"))
      (node (ref "U$11") (pin "B") (pinfunction "3_B") (pintype "bidirectional"))
      (node (ref "U$12") (pin "B") (pinfunction "3_B") (pintype "bidirectional"))
      (node (ref "U$13") (pin "B") (pinfunction "3_B") (pintype "bidirectional"))
      (node (ref "U$14") (pin "B") (pinfunction "3_B") (pintype "bidirectional"))
      (node (ref "U$15") (pin "B") (pinfunction "3_B") (pintype "bidirectional"))
      (node (ref "U$16") (pin "B") (pinfunction "3_B") (pintype "bidirectional"))
      (node (ref "U$2") (pin "B") (pinfunction "3_B") (pintype "bidirectional"))
      (node (ref "U$3") (pin "B") (pinfunction "3_B") (pintype "bidirectional"))
      (node (ref "U$4") (pin "B") (pinfunction "3_B") (pintype "bidirectional"))
      (node (ref "U$5") (pin "B") (pinfunction "3_B") (pintype "bidirectional"))
      (node (ref "U$6") (pin "B") (pinfunction "3_B") (pintype "bidirectional"))
      (node (ref "U$7") (pin "B") (pinfunction "3_B") (pintype "bidirectional"))
      (node (ref "U$8") (pin "B") (pinfunction "3_B") (pintype "bidirectional"))
      (node (ref "U$9") (pin "B") (pinfunction "3_B") (pintype "bidirectional"))
      (node (ref "V1") (pin "2") (pinfunction "GND_2") (pintype "power_in"))
      (node (ref "V100") (pin "2") (pinfunction "-VIN_2") (pintype "passive"))
      (node (ref "V100") (pin "3") (pinfunction "-VOUT_3") (pintype "passive"))
      (node (ref "V2") (pin "GND") (pinfunction "GND_GND") (pintype "input"))
    )
    (net (code "43") (name "MIDI_OUT") (class "Default")
      (node (ref "IC10") (pin "1") (pinfunction "1/TX1/T_1") (pintype "bidirectional"))
      (node (ref "R83") (pin "2") (pinfunction "2_2") (pintype "passive"))
    )
    (net (code "44") (name "Net-(IC1A-+IN)") (class "Default")
      (node (ref "IC1") (pin "3") (pinfunction "+IN_3") (pintype "input"))
      (node (ref "JP115") (pin "1") (pinfunction "1_1") (pintype "passive"))
      (node (ref "R17") (pin "1") (pinfunction "1_1") (pintype "passive"))
    )
    (net (code "45") (name "Net-(IC1A--IN)") (class "Default")
      (node (ref "IC1") (pin "1") (pinfunction "OUT_1") (pintype "output"))
      (node (ref "IC1") (pin "2") (pinfunction "-IN_2") (pintype "input"))
      (node (ref "R1") (pin "1") (pinfunction "1_1") (pintype "passive"))
    )
    (net (code "46") (name "Net-(IC1B-+IN)") (class "Default")
      (node (ref "IC1") (pin "5") (pinfunction "+IN_5") (pintype "input"))
      (node (ref "JP114") (pin "1") (pinfunction "1_1") (pintype "passive"))
      (node (ref "R18") (pin "1") (pinfunction "1_1") (pintype "passive"))
    )
    (net (code "47") (name "Net-(IC1B--IN)") (class "Default")
      (node (ref "IC1") (pin "6") (pinfunction "-IN_6") (pintype "input"))
      (node (ref "IC1") (pin "7") (pinfunction "OUT_7") (pintype "output"))
      (node (ref "R2") (pin "1") (pinfunction "1_1") (pintype "passive"))
    )
    (net (code "48") (name "Net-(IC1C-+IN)") (class "Default")
      (node (ref "IC1") (pin "12") (pinfunction "+IN_12") (pintype "input"))
      (node (ref "JP112") (pin "1") (pinfunction "1_1") (pintype "passive"))
      (node (ref "R20") (pin "1") (pinfunction "1_1") (pintype "passive"))
    )
    (net (code "49") (name "Net-(IC1C--IN)") (class "Default")
      (node (ref "IC1") (pin "13") (pinfunction "-IN_13") (pintype "input"))
      (node (ref "IC1") (pin "14") (pinfunction "OUT_14") (pintype "output"))
      (node (ref "R4") (pin "1") (pinfunction "1_1") (pintype "passive"))
    )
    (net (code "50") (name "Net-(IC1D-+IN)") (class "Default")
      (node (ref "IC1") (pin "10") (pinfunction "+IN_10") (pintype "input"))
      (node (ref "JP113") (pin "1") (pinfunction "1_1") (pintype "passive"))
      (node (ref "R19") (pin "1") (pinfunction "1_1") (pintype "passive"))
    )
    (net (code "51") (name "Net-(IC1D--IN)") (class "Default")
      (node (ref "IC1") (pin "8") (pinfunction "OUT_8") (pintype "output"))
      (node (ref "IC1") (pin "9") (pinfunction "-IN_9") (pintype "input"))
      (node (ref "R3") (pin "1") (pinfunction "1_1") (pintype "passive"))
    )
    (net (code "52") (name "Net-(IC2A-+IN)") (class "Default")
      (node (ref "IC2") (pin "3") (pinfunction "+IN_3") (pintype "input"))
      (node (ref "JP111") (pin "1") (pinfunction "1_1") (pintype "passive"))
      (node (ref "R21") (pin "1") (pinfunction "1_1") (pintype "passive"))
    )
    (net (code "53") (name "Net-(IC2A--IN)") (class "Default")
      (node (ref "IC2") (pin "1") (pinfunction "OUT_1") (pintype "output"))
      (node (ref "IC2") (pin "2") (pinfunction "-IN_2") (pintype "input"))
      (node (ref "R5") (pin "1") (pinfunction "1_1") (pintype "passive"))
    )
    (net (code "54") (name "Net-(IC2B-+IN)") (class "Default")
      (node (ref "IC2") (pin "5") (pinfunction "+IN_5") (pintype "input"))
      (node (ref "JP110") (pin "1") (pinfunction "1_1") (pintype "passive"))
      (node (ref "R22") (pin "1") (pinfunction "1_1") (pintype "passive"))
    )
    (net (code "55") (name "Net-(IC2B--IN)") (class "Default")
      (node (ref "IC2") (pin "6") (pinfunction "-IN_6") (pintype "input"))
      (node (ref "IC2") (pin "7") (pinfunction "OUT_7") (pintype "output"))
      (node (ref "R6") (pin "1") (pinfunction "1_1") (pintype "passive"))
    )
    (net (code "56") (name "Net-(IC2C-+IN)") (class "Default")
      (node (ref "IC2") (pin "12") (pinfunction "+IN_12") (pintype "input"))
      (node (ref "JP108") (pin "1") (pinfunction "1_1") (pintype "passive"))
      (node (ref "R24") (pin "1") (pinfunction "1_1") (pintype "passive"))
    )
    (net (code "57") (name "Net-(IC2C--IN)") (class "Default")
      (node (ref "IC2") (pin "13") (pinfunction "-IN_13") (pintype "input"))
      (node (ref "IC2") (pin "14") (pinfunction "OUT_14") (pintype "output"))
      (node (ref "R8") (pin "1") (pinfunction "1_1") (pintype "passive"))
    )
    (net (code "58") (name "Net-(IC2D-+IN)") (class "Default")
      (node (ref "IC2") (pin "10") (pinfunction "+IN_10") (pintype "input"))
      (node (ref "JP109") (pin "1") (pinfunction "1_1") (pintype "passive"))
      (node (ref "R23") (pin "1") (pinfunction "1_1") (pintype "passive"))
    )
    (net (code "59") (name "Net-(IC2D--IN)") (class "Default")
      (node (ref "IC2") (pin "8") (pinfunction "OUT_8") (pintype "output"))
      (node (ref "IC2") (pin "9") (pinfunction "-IN_9") (pintype "input"))
      (node (ref "R7") (pin "1") (pinfunction "1_1") (pintype "passive"))
    )
    (net (code "60") (name "Net-(IC3A-+IN)") (class "Default")
      (node (ref "IC3") (pin "3") (pinfunction "+IN_3") (pintype "input"))
      (node (ref "JP107") (pin "1") (pinfunction "1_1") (pintype "passive"))
      (node (ref "R25") (pin "1") (pinfunction "1_1") (pintype "passive"))
    )
    (net (code "61") (name "Net-(IC3A--IN)") (class "Default")
      (node (ref "IC3") (pin "1") (pinfunction "OUT_1") (pintype "output"))
      (node (ref "IC3") (pin "2") (pinfunction "-IN_2") (pintype "input"))
      (node (ref "R9") (pin "1") (pinfunction "1_1") (pintype "passive"))
    )
    (net (code "62") (name "Net-(IC3B-+IN)") (class "Default")
      (node (ref "IC3") (pin "5") (pinfunction "+IN_5") (pintype "input"))
      (node (ref "JP106") (pin "1") (pinfunction "1_1") (pintype "passive"))
      (node (ref "R26") (pin "1") (pinfunction "1_1") (pintype "passive"))
    )
    (net (code "63") (name "Net-(IC3B--IN)") (class "Default")
      (node (ref "IC3") (pin "6") (pinfunction "-IN_6") (pintype "input"))
      (node (ref "IC3") (pin "7") (pinfunction "OUT_7") (pintype "output"))
      (node (ref "R10") (pin "1") (pinfunction "1_1") (pintype "passive"))
    )
    (net (code "64") (name "Net-(IC3C-+IN)") (class "Default")
      (node (ref "IC3") (pin "12") (pinfunction "+IN_12") (pintype "input"))
      (node (ref "JP104") (pin "1") (pinfunction "1_1") (pintype "passive"))
      (node (ref "R28") (pin "1") (pinfunction "1_1") (pintype "passive"))
    )
    (net (code "65") (name "Net-(IC3C--IN)") (class "Default")
      (node (ref "IC3") (pin "13") (pinfunction "-IN_13") (pintype "input"))
      (node (ref "IC3") (pin "14") (pinfunction "OUT_14") (pintype "output"))
      (node (ref "R12") (pin "1") (pinfunction "1_1") (pintype "passive"))
    )
    (net (code "66") (name "Net-(IC3D-+IN)") (class "Default")
      (node (ref "IC3") (pin "10") (pinfunction "+IN_10") (pintype "input"))
      (node (ref "JP105") (pin "1") (pinfunction "1_1") (pintype "passive"))
      (node (ref "R27") (pin "1") (pinfunction "1_1") (pintype "passive"))
    )
    (net (code "67") (name "Net-(IC3D--IN)") (class "Default")
      (node (ref "IC3") (pin "8") (pinfunction "OUT_8") (pintype "output"))
      (node (ref "IC3") (pin "9") (pinfunction "-IN_9") (pintype "input"))
      (node (ref "R11") (pin "1") (pinfunction "1_1") (pintype "passive"))
    )
    (net (code "68") (name "Net-(IC4A-+IN)") (class "Default")
      (node (ref "IC4") (pin "3") (pinfunction "+IN_3") (pintype "input"))
      (node (ref "JP103") (pin "1") (pinfunction "1_1") (pintype "passive"))
      (node (ref "R29") (pin "1") (pinfunction "1_1") (pintype "passive"))
    )
    (net (code "69") (name "Net-(IC4A--IN)") (class "Default")
      (node (ref "IC4") (pin "1") (pinfunction "OUT_1") (pintype "output"))
      (node (ref "IC4") (pin "2") (pinfunction "-IN_2") (pintype "input"))
      (node (ref "R13") (pin "1") (pinfunction "1_1") (pintype "passive"))
    )
    (net (code "70") (name "Net-(IC4B-+IN)") (class "Default")
      (node (ref "IC4") (pin "5") (pinfunction "+IN_5") (pintype "input"))
      (node (ref "JP102") (pin "1") (pinfunction "1_1") (pintype "passive"))
      (node (ref "R30") (pin "1") (pinfunction "1_1") (pintype "passive"))
    )
    (net (code "71") (name "Net-(IC4B--IN)") (class "Default")
      (node (ref "IC4") (pin "6") (pinfunction "-IN_6") (pintype "input"))
      (node (ref "IC4") (pin "7") (pinfunction "OUT_7") (pintype "output"))
      (node (ref "R14") (pin "1") (pinfunction "1_1") (pintype "passive"))
    )
    (net (code "72") (name "Net-(IC4C-+IN)") (class "Default")
      (node (ref "IC4") (pin "12") (pinfunction "+IN_12") (pintype "input"))
      (node (ref "JP100") (pin "1") (pinfunction "1_1") (pintype "passive"))
      (node (ref "R32") (pin "1") (pinfunction "1_1") (pintype "passive"))
    )
    (net (code "73") (name "Net-(IC4C--IN)") (class "Default")
      (node (ref "IC4") (pin "13") (pinfunction "-IN_13") (pintype "input"))
      (node (ref "IC4") (pin "14") (pinfunction "OUT_14") (pintype "output"))
      (node (ref "R16") (pin "1") (pinfunction "1_1") (pintype "passive"))
    )
    (net (code "74") (name "Net-(IC4D-+IN)") (class "Default")
      (node (ref "IC4") (pin "10") (pinfunction "+IN_10") (pintype "input"))
      (node (ref "JP101") (pin "1") (pinfunction "1_1") (pintype "passive"))
      (node (ref "R31") (pin "1") (pinfunction "1_1") (pintype "passive"))
    )
    (net (code "75") (name "Net-(IC4D--IN)") (class "Default")
      (node (ref "IC4") (pin "8") (pinfunction "OUT_8") (pintype "output"))
      (node (ref "IC4") (pin "9") (pinfunction "-IN_9") (pintype "input"))
      (node (ref "R15") (pin "1") (pinfunction "1_1") (pintype "passive"))
    )
    (net (code "76") (name "Net-(IC5A-+IN)") (class "Default")
      (node (ref "IC5") (pin "3") (pinfunction "+IN_3") (pintype "input"))
      (node (ref "R55") (pin "2") (pinfunction "2_2") (pintype "passive"))
      (node (ref "R56") (pin "2") (pinfunction "2_2") (pintype "passive"))
    )
    (net (code "77") (name "Net-(IC5B-+IN)") (class "Default")
      (node (ref "IC5") (pin "5") (pinfunction "+IN_5") (pintype "input"))
      (node (ref "R71") (pin "2") (pinfunction "2_2") (pintype "passive"))
      (node (ref "R72") (pin "2") (pinfunction "2_2") (pintype "passive"))
    )
    (net (code "78") (name "Net-(IC5C-+IN)") (class "Default")
      (node (ref "IC5") (pin "10") (pinfunction "+IN_10") (pintype "input"))
      (node (ref "R69") (pin "2") (pinfunction "2_2") (pintype "passive"))
      (node (ref "R70") (pin "2") (pinfunction "2_2") (pintype "passive"))
    )
    (net (code "79") (name "Net-(IC5D-+IN)") (class "Default")
      (node (ref "IC5") (pin "12") (pinfunction "+IN_12") (pintype "input"))
      (node (ref "R53") (pin "2") (pinfunction "2_2") (pintype "passive"))
      (node (ref "R54") (pin "2") (pinfunction "2_2") (pintype "passive"))
    )
    (net (code "80") (name "Net-(IC6A-+IN)") (class "Default")
      (node (ref "IC6") (pin "3") (pinfunction "+IN_3") (pintype "input"))
      (node (ref "R59") (pin "2") (pinfunction "2_2") (pintype "passive"))
      (node (ref "R60") (pin "2") (pinfunction "2_2") (pintype "passive"))
    )
    (net (code "81") (name "Net-(IC6B-+IN)") (class "Default")
      (node (ref "IC6") (pin "5") (pinfunction "+IN_5") (pintype "input"))
      (node (ref "R75") (pin "2") (pinfunction "2_2") (pintype "passive"))
      (node (ref "R76") (pin "2") (pinfunction "2_2") (pintype "passive"))
    )
    (net (code "82") (name "Net-(IC6C-+IN)") (class "Default")
      (node (ref "IC6") (pin "10") (pinfunction "+IN_10") (pintype "input"))
      (node (ref "R73") (pin "2") (pinfunction "2_2") (pintype "passive"))
      (node (ref "R74") (pin "2") (pinfunction "2_2") (pintype "passive"))
    )
    (net (code "83") (name "Net-(IC6D-+IN)") (class "Default")
      (node (ref "IC6") (pin "12") (pinfunction "+IN_12") (pintype "input"))
      (node (ref "R57") (pin "2") (pinfunction "2_2") (pintype "passive"))
      (node (ref "R58") (pin "2") (pinfunction "2_2") (pintype "passive"))
    )
    (net (code "84") (name "Net-(IC7A-+IN)") (class "Default")
      (node (ref "IC7") (pin "3") (pinfunction "+IN_3") (pintype "input"))
      (node (ref "R63") (pin "2") (pinfunction "2_2") (pintype "passive"))
      (node (ref "R64") (pin "2") (pinfunction "2_2") (pintype "passive"))
    )
    (net (code "85") (name "Net-(IC7B-+IN)") (class "Default")
      (node (ref "IC7") (pin "5") (pinfunction "+IN_5") (pintype "input"))
      (node (ref "R79") (pin "2") (pinfunction "2_2") (pintype "passive"))
      (node (ref "R80") (pin "2") (pinfunction "2_2") (pintype "passive"))
    )
    (net (code "86") (name "Net-(IC7C-+IN)") (class "Default")
      (node (ref "IC7") (pin "10") (pinfunction "+IN_10") (pintype "input"))
      (node (ref "R77") (pin "2") (pinfunction "2_2") (pintype "passive"))
      (node (ref "R78") (pin "2") (pinfunction "2_2") (pintype "passive"))
    )
    (net (code "87") (name "Net-(IC7D-+IN)") (class "Default")
      (node (ref "IC7") (pin "12") (pinfunction "+IN_12") (pintype "input"))
      (node (ref "R61") (pin "2") (pinfunction "2_2") (pintype "passive"))
      (node (ref "R62") (pin "2") (pinfunction "2_2") (pintype "passive"))
    )
    (net (code "88") (name "Net-(IC8A-+IN)") (class "Default")
      (node (ref "IC8") (pin "3") (pinfunction "+IN_3") (pintype "input"))
      (node (ref "R51") (pin "2") (pinfunction "2_2") (pintype "passive"))
      (node (ref "R52") (pin "2") (pinfunction "2_2") (pintype "passive"))
    )
    (net (code "89") (name "Net-(IC8B-+IN)") (class "Default")
      (node (ref "IC8") (pin "5") (pinfunction "+IN_5") (pintype "input"))
      (node (ref "R67") (pin "2") (pinfunction "2_2") (pintype "passive"))
      (node (ref "R68") (pin "2") (pinfunction "2_2") (pintype "passive"))
    )
    (net (code "90") (name "Net-(IC8C-+IN)") (class "Default")
      (node (ref "IC8") (pin "10") (pinfunction "+IN_10") (pintype "input"))
      (node (ref "R81") (pin "2") (pinfunction "2_2") (pintype "passive"))
      (node (ref "R82") (pin "2") (pinfunction "2_2") (pintype "passive"))
    )
    (net (code "91") (name "Net-(JP2-LEFT)") (class "Default")
      (node (ref "JP2") (pin "P$1_TIP") (pinfunction "LEFT_P$1_TIP") (pintype "bidirectional"))
      (node (ref "S100") (pin "P2") (pinfunction "5_P2") (pintype "bidirectional"))
    )
    (net (code "92") (name "Net-(JP2-RIGHT)") (class "Default")
      (node (ref "JP2") (pin "P$2_SWITCH") (pinfunction "RIGHT_P$2_SWITCH") (pintype "bidirectional"))
      (node (ref "S100") (pin "P1") (pinfunction "2_P1") (pintype "bidirectional"))
    )
    (net (code "93") (name "Net-(JP100-Pad2)") (class "Default")
      (node (ref "JP100") (pin "2") (pinfunction "2_2") (pintype "passive"))
      (node (ref "R48") (pin "1") (pinfunction "1_1") (pintype "passive"))
    )
    (net (code "94") (name "Net-(JP101-Pad2)") (class "Default")
      (node (ref "JP101") (pin "2") (pinfunction "2_2") (pintype "passive"))
      (node (ref "R47") (pin "1") (pinfunction "1_1") (pintype "passive"))
    )
    (net (code "95") (name "Net-(JP102-Pad2)") (class "Default")
      (node (ref "JP102") (pin "2") (pinfunction "2_2") (pintype "passive"))
      (node (ref "R46") (pin "1") (pinfunction "1_1") (pintype "passive"))
    )
    (net (code "96") (name "Net-(JP103-Pad2)") (class "Default")
      (node (ref "JP103") (pin "2") (pinfunction "2_2") (pintype "passive"))
      (node (ref "R45") (pin "1") (pinfunction "1_1") (pintype "passive"))
    )
    (net (code "97") (name "Net-(JP104-Pad2)") (class "Default")
      (node (ref "JP104") (pin "2") (pinfunction "2_2") (pintype "passive"))
      (node (ref "R44") (pin "1") (pinfunction "1_1") (pintype "passive"))
    )
    (net (code "98") (name "Net-(JP105-Pad2)") (class "Default")
      (node (ref "JP105") (pin "2") (pinfunction "2_2") (pintype "passive"))
      (node (ref "R43") (pin "1") (pinfunction "1_1") (pintype "passive"))
    )
    (net (code "99") (name "Net-(JP106-Pad2)") (class "Default")
      (node (ref "JP106") (pin "2") (pinfunction "2_2") (pintype "passive"))
      (node (ref "R42") (pin "1") (pinfunction "1_1") (pintype "passive"))
    )
    (net (code "100") (name "Net-(JP107-Pad2)") (class "Default")
      (node (ref "JP107") (pin "2") (pinfunction "2_2") (pintype "passive"))
      (node (ref "R41") (pin "1") (pinfunction "1_1") (pintype "passive"))
    )
    (net (code "101") (name "Net-(JP108-Pad2)") (class "Default")
      (node (ref "JP108") (pin "2") (pinfunction "2_2") (pintype "passive"))
      (node (ref "R40") (pin "1") (pinfunction "1_1") (pintype "passive"))
    )
    (net (code "102") (name "Net-(JP109-Pad2)") (class "Default")
      (node (ref "JP109") (pin "2") (pinfunction "2_2") (pintype "passive"))
      (node (ref "R39") (pin "1") (pinfunction "1_1") (pintype "passive"))
    )
    (net (code "103") (name "Net-(JP110-Pad2)") (class "Default")
      (node (ref "JP110") (pin "2") (pinfunction "2_2") (pintype "passive"))
      (node (ref "R38") (pin "1") (pinfunction "1_1") (pintype "passive"))
    )
    (net (code "104") (name "Net-(JP111-Pad2)") (class "Default")
      (node (ref "JP111") (pin "2") (pinfunction "2_2") (pintype "passive"))
      (node (ref "R37") (pin "1") (pinfunction "1_1") (pintype "passive"))
    )
    (net (code "105") (name "Net-(JP112-Pad2)") (class "Default")
      (node (ref "JP112") (pin "2") (pinfunction "2_2") (pintype "passive"))
      (node (ref "R36") (pin "1") (pinfunction "1_1") (pintype "passive"))
    )
    (net (code "106") (name "Net-(JP113-Pad2)") (class "Default")
      (node (ref "JP113") (pin "2") (pinfunction "2_2") (pintype "passive"))
      (node (ref "R35") (pin "1") (pinfunction "1_1") (pintype "passive"))
    )
    (net (code "107") (name "Net-(JP114-Pad2)") (class "Default")
      (node (ref "JP114") (pin "2") (pinfunction "2_2") (pintype "passive"))
      (node (ref "R34") (pin "1") (pinfunction "1_1") (pintype "passive"))
    )
    (net (code "108") (name "Net-(JP115-Pad2)") (class "Default")
      (node (ref "JP115") (pin "2") (pinfunction "2_2") (pintype "passive"))
      (node (ref "R33") (pin "1") (pinfunction "1_1") (pintype "passive"))
    )
    (net (code "109") (name "Net-(LED1-PadA)") (class "Default")
      (node (ref "LED1") (pin "A") (pinfunction "A_A") (pintype "passive"))
      (node (ref "R84") (pin "1") (pinfunction "1_1") (pintype "passive"))
    )
    (net (code "110") (name "Net-(S100-1)") (class "Default")
      (node (ref "R85") (pin "1") (pinfunction "1_1") (pintype "passive"))
      (node (ref "S100") (pin "P1-TA") (pinfunction "1_P1-TA") (pintype "bidirectional"))
      (node (ref "S100") (pin "P2-TB") (pinfunction "6_P2-TB") (pintype "bidirectional"))
    )
    (net (code "111") (name "Net-(S100-3)") (class "Default")
      (node (ref "R83") (pin "1") (pinfunction "1_1") (pintype "passive"))
      (node (ref "S100") (pin "P1-TB") (pinfunction "3_P1-TB") (pintype "bidirectional"))
      (node (ref "S100") (pin "P2-TA") (pinfunction "4_P2-TA") (pintype "bidirectional"))
    )
    (net (code "112") (name "Net-(V1-BYPASS)") (class "Default")
      (node (ref "C3") (pin "1") (pinfunction "1_1") (pintype "passive"))
      (node (ref "V1") (pin "4") (pinfunction "BYPASS_4") (pintype "passive"))
    )
    (net (code "113") (name "S$2") (class "Default")
      (node (ref "IC8") (pin "12") (pinfunction "+IN_12") (pintype "input"))
      (node (ref "R65") (pin "2") (pinfunction "2_2") (pintype "passive"))
      (node (ref "R66") (pin "2") (pinfunction "2_2") (pintype "passive"))
    )
    (net (code "114") (name "S0") (class "Default")
      (node (ref "IC10") (pin "8") (pinfunction "8/TX3_8") (pintype "bidirectional"))
      (node (ref "IC9") (pin "10") (pinfunction "S0_10") (pintype "input"))
    )
    (net (code "115") (name "S1") (class "Default")
      (node (ref "IC10") (pin "7") (pinfunction "7/RX3_7") (pintype "bidirectional"))
      (node (ref "IC9") (pin "11") (pinfunction "S1_11") (pintype "input"))
    )
    (net (code "116") (name "S2") (class "Default")
      (node (ref "IC10") (pin "6") (pinfunction "6/PWM_6") (pintype "bidirectional"))
      (node (ref "IC9") (pin "14") (pinfunction "S2_14") (pintype "input"))
    )
    (net (code "117") (name "S3") (class "Default")
      (node (ref "IC10") (pin "5") (pinfunction "5/PWM_5") (pintype "bidirectional"))
      (node (ref "IC9") (pin "13") (pinfunction "S3_13") (pintype "input"))
    )
    (net (code "118") (name "SCL") (class "Default")
      (node (ref "D2") (pin "A") (pinfunction "A_A") (pintype "passive"))
      (node (ref "D3") (pin "C") (pinfunction "C_C") (pintype "passive"))
      (node (ref "I2C") (pin "2") (pinfunction "2_2") (pintype "passive"))
      (node (ref "IC10") (pin "19/A5") (pinfunction "19/A5/T/SCL0_19/A5") (pintype "bidirectional"))
      (node (ref "JP1") (pin "P$2_SWITCH") (pinfunction "RIGHT_P$2_SWITCH") (pintype "bidirectional"))
      (node (ref "R49") (pin "1") (pinfunction "1_1") (pintype "passive"))
    )
    (net (code "119") (name "SDA") (class "Default")
      (node (ref "D4") (pin "C") (pinfunction "C_C") (pintype "passive"))
      (node (ref "D5") (pin "A") (pinfunction "A_A") (pintype "passive"))
      (node (ref "I2C") (pin "1") (pinfunction "1_1") (pintype "passive"))
      (node (ref "IC10") (pin "18/A4") (pinfunction "18/A4/T/SDA0_18/A4") (pintype "bidirectional"))
      (node (ref "JP1") (pin "P$1_TIP") (pinfunction "LEFT_P$1_TIP") (pintype "bidirectional"))
      (node (ref "R50") (pin "1") (pinfunction "1_1") (pintype "passive"))
    )
    (net (code "120") (name "W0") (class "Default")
      (node (ref "R17") (pin "2") (pinfunction "2_2") (pintype "passive"))
      (node (ref "R69") (pin "1") (pinfunction "1_1") (pintype "passive"))
      (node (ref "U$1") (pin "WIPER") (pinfunction "2_WIPER") (pintype "bidirectional"))
    )
    (net (code "121") (name "W1") (class "Default")
      (node (ref "R18") (pin "2") (pinfunction "2_2") (pintype "passive"))
      (node (ref "R53") (pin "1") (pinfunction "1_1") (pintype "passive"))
      (node (ref "U$2") (pin "WIPER") (pinfunction "2_WIPER") (pintype "bidirectional"))
    )
    (net (code "122") (name "W2") (class "Default")
      (node (ref "R19") (pin "2") (pinfunction "2_2") (pintype "passive"))
      (node (ref "R71") (pin "1") (pinfunction "1_1") (pintype "passive"))
      (node (ref "U$3") (pin "WIPER") (pinfunction "2_WIPER") (pintype "bidirectional"))
    )
    (net (code "123") (name "W3") (class "Default")
      (node (ref "R20") (pin "2") (pinfunction "2_2") (pintype "passive"))
      (node (ref "R55") (pin "1") (pinfunction "1_1") (pintype "passive"))
      (node (ref "U$4") (pin "WIPER") (pinfunction "2_WIPER") (pintype "bidirectional"))
    )
    (net (code "124") (name "W4") (class "Default")
      (node (ref "R21") (pin "2") (pinfunction "2_2") (pintype "passive"))
      (node (ref "R73") (pin "1") (pinfunction "1_1") (pintype "passive"))
      (node (ref "U$5") (pin "WIPER") (pinfunction "2_WIPER") (pintype "bidirectional"))
    )
    (net (code "125") (name "W5") (class "Default")
      (node (ref "R22") (pin "2") (pinfunction "2_2") (pintype "passive"))
      (node (ref "R57") (pin "1") (pinfunction "1_1") (pintype "passive"))
      (node (ref "U$6") (pin "WIPER") (pinfunction "2_WIPER") (pintype "bidirectional"))
    )
    (net (code "126") (name "W6") (class "Default")
      (node (ref "R23") (pin "2") (pinfunction "2_2") (pintype "passive"))
      (node (ref "R75") (pin "1") (pinfunction "1_1") (pintype "passive"))
      (node (ref "U$7") (pin "WIPER") (pinfunction "2_WIPER") (pintype "bidirectional"))
    )
    (net (code "127") (name "W7") (class "Default")
      (node (ref "R24") (pin "2") (pinfunction "2_2") (pintype "passive"))
      (node (ref "R59") (pin "1") (pinfunction "1_1") (pintype "passive"))
      (node (ref "U$8") (pin "WIPER") (pinfunction "2_WIPER") (pintype "bidirectional"))
    )
    (net (code "128") (name "W8") (class "Default")
      (node (ref "R25") (pin "2") (pinfunction "2_2") (pintype "passive"))
      (node (ref "R77") (pin "1") (pinfunction "1_1") (pintype "passive"))
      (node (ref "U$9") (pin "WIPER") (pinfunction "2_WIPER") (pintype "bidirectional"))
    )
    (net (code "129") (name "W9") (class "Default")
      (node (ref "R26") (pin "2") (pinfunction "2_2") (pintype "passive"))
      (node (ref "R61") (pin "1") (pinfunction "1_1") (pintype "passive"))
      (node (ref "U$10") (pin "WIPER") (pinfunction "2_WIPER") (pintype "bidirectional"))
    )
    (net (code "130") (name "W10") (class "Default")
      (node (ref "R27") (pin "2") (pinfunction "2_2") (pintype "passive"))
      (node (ref "R79") (pin "1") (pinfunction "1_1") (pintype "passive"))
      (node (ref "U$11") (pin "WIPER") (pinfunction "2_WIPER") (pintype "bidirectional"))
    )
    (net (code "131") (name "W11") (class "Default")
      (node (ref "R28") (pin "2") (pinfunction "2_2") (pintype "passive"))
      (node (ref "R63") (pin "1") (pinfunction "1_1") (pintype "passive"))
      (node (ref "U$12") (pin "WIPER") (pinfunction "2_WIPER") (pintype "bidirectional"))
    )
    (net (code "132") (name "W12") (class "Default")
      (node (ref "R29") (pin "2") (pinfunction "2_2") (pintype "passive"))
      (node (ref "R81") (pin "1") (pinfunction "1_1") (pintype "passive"))
      (node (ref "U$13") (pin "WIPER") (pinfunction "2_WIPER") (pintype "bidirectional"))
    )
    (net (code "133") (name "W13") (class "Default")
      (node (ref "R30") (pin "2") (pinfunction "2_2") (pintype "passive"))
      (node (ref "R65") (pin "1") (pinfunction "1_1") (pintype "passive"))
      (node (ref "U$14") (pin "WIPER") (pinfunction "2_WIPER") (pintype "bidirectional"))
    )
    (net (code "134") (name "W14") (class "Default")
      (node (ref "R31") (pin "2") (pinfunction "2_2") (pintype "passive"))
      (node (ref "R67") (pin "1") (pinfunction "1_1") (pintype "passive"))
      (node (ref "U$15") (pin "WIPER") (pinfunction "2_WIPER") (pintype "bidirectional"))
    )
    (net (code "135") (name "W15") (class "Default")
      (node (ref "R32") (pin "2") (pinfunction "2_2") (pintype "passive"))
      (node (ref "R51") (pin "1") (pinfunction "1_1") (pintype "passive"))
      (node (ref "U$16") (pin "WIPER") (pinfunction "2_WIPER") (pintype "bidirectional"))
    )
    (net (code "136") (name "unconnected-(IC10-0{slash}RX1{slash}T-Pad0)") (class "Default")
      (node (ref "IC10") (pin "0") (pinfunction "0/RX1/T_0") (pintype "bidirectional"))
    )
    (net (code "137") (name "unconnected-(IC10-3{slash}CAN-TX{slash}PWM-Pad3)") (class "Default")
      (node (ref "IC10") (pin "3") (pinfunction "3/CAN-TX/PWM_3") (pintype "bidirectional"))
    )
    (net (code "138") (name "unconnected-(IC10-4{slash}CAN-RX{slash}PWM-Pad4)") (class "Default")
      (node (ref "IC10") (pin "4") (pinfunction "4/CAN-RX/PWM_4") (pintype "bidirectional"))
    )
    (net (code "139") (name "unconnected-(IC10-9{slash}RX2{slash}PWM-Pad9)") (class "Default")
      (node (ref "IC10") (pin "9") (pinfunction "9/RX2/PWM_9") (pintype "bidirectional"))
    )
    (net (code "140") (name "unconnected-(IC10-10{slash}TX2{slash}PWM-Pad10)") (class "Default")
      (node (ref "IC10") (pin "10") (pinfunction "10/TX2/PWM_10") (pintype "bidirectional"))
    )
    (net (code "141") (name "unconnected-(IC10-11{slash}MOSI-Pad11)") (class "Default")
      (node (ref "IC10") (pin "11") (pinfunction "11/MOSI_11") (pintype "bidirectional"))
    )
    (net (code "142") (name "unconnected-(IC10-12{slash}MISO-Pad12)") (class "Default")
      (node (ref "IC10") (pin "12") (pinfunction "12/MISO_12") (pintype "bidirectional"))
    )
    (net (code "143") (name "unconnected-(IC10-13{slash}SCK{slash}LED-Pad13)") (class "Default")
      (node (ref "IC10") (pin "13") (pinfunction "13/SCK/LED_13") (pintype "bidirectional"))
    )
    (net (code "144") (name "unconnected-(IC10-15{slash}A1{slash}T-Pad15{slash}A1)") (class "Default")
      (node (ref "IC10") (pin "15/A1") (pinfunction "15/A1/T_15/A1") (pintype "bidirectional"))
    )
    (net (code "145") (name "unconnected-(IC10-16{slash}A2{slash}T-Pad16{slash}A2)") (class "Default")
      (node (ref "IC10") (pin "16/A2") (pinfunction "16/A2/T_16/A2") (pintype "bidirectional"))
    )
    (net (code "146") (name "unconnected-(IC10-17{slash}A3{slash}T-Pad17{slash}A3)") (class "Default")
      (node (ref "IC10") (pin "17/A3") (pinfunction "17/A3/T_17/A3") (pintype "bidirectional"))
    )
    (net (code "147") (name "unconnected-(IC10-20{slash}A6{slash}PWM-Pad20{slash}A6)") (class "Default")
      (node (ref "IC10") (pin "20/A6") (pinfunction "20/A6/PWM_20/A6") (pintype "bidirectional"))
    )
    (net (code "148") (name "unconnected-(IC10-21{slash}A7{slash}PWM-Pad21{slash}A7)") (class "Default")
      (node (ref "IC10") (pin "21/A7") (pinfunction "21/A7/PWM_21/A7") (pintype "bidirectional"))
    )
    (net (code "149") (name "unconnected-(IC10-22{slash}A8{slash}T{slash}PWM-Pad22{slash}A8)") (class "Default")
      (node (ref "IC10") (pin "22/A8") (pinfunction "22/A8/T/PWM_22/A8") (pintype "bidirectional"))
    )
    (net (code "150") (name "unconnected-(IC10-23{slash}A9{slash}T{slash}PWM-Pad23{slash}A9)") (class "Default")
      (node (ref "IC10") (pin "23/A9") (pinfunction "23/A9/T/PWM_23/A9") (pintype "bidirectional"))
    )
    (net (code "151") (name "unconnected-(IC10-Pad2)") (class "Default")
      (node (ref "IC10") (pin "2") (pinfunction "2_2") (pintype "bidirectional"))
    )
    (net (code "152") (name "unconnected-(J1-SWITCH-PadP$2_SWITCH)") (class "Default")
      (node (ref "J1") (pin "P$2_SWITCH") (pinfunction "SWITCH_P$2_SWITCH") (pintype "passive"))
    )
    (net (code "153") (name "unconnected-(J2-SWITCH-PadP$2_SWITCH)") (class "Default")
      (node (ref "J2") (pin "P$2_SWITCH") (pinfunction "SWITCH_P$2_SWITCH") (pintype "passive"))
    )
    (net (code "154") (name "unconnected-(J3-SWITCH-PadP$2_SWITCH)") (class "Default")
      (node (ref "J3") (pin "P$2_SWITCH") (pinfunction "SWITCH_P$2_SWITCH") (pintype "passive"))
    )
    (net (code "155") (name "unconnected-(J4-SWITCH-PadP$2_SWITCH)") (class "Default")
      (node (ref "J4") (pin "P$2_SWITCH") (pinfunction "SWITCH_P$2_SWITCH") (pintype "passive"))
    )
    (net (code "156") (name "unconnected-(J5-SWITCH-PadP$2_SWITCH)") (class "Default")
      (node (ref "J5") (pin "P$2_SWITCH") (pinfunction "SWITCH_P$2_SWITCH") (pintype "passive"))
    )
    (net (code "157") (name "unconnected-(J6-SWITCH-PadP$2_SWITCH)") (class "Default")
      (node (ref "J6") (pin "P$2_SWITCH") (pinfunction "SWITCH_P$2_SWITCH") (pintype "passive"))
    )
    (net (code "158") (name "unconnected-(J7-SWITCH-PadP$2_SWITCH)") (class "Default")
      (node (ref "J7") (pin "P$2_SWITCH") (pinfunction "SWITCH_P$2_SWITCH") (pintype "passive"))
    )
    (net (code "159") (name "unconnected-(J8-SWITCH-PadP$2_SWITCH)") (class "Default")
      (node (ref "J8") (pin "P$2_SWITCH") (pinfunction "SWITCH_P$2_SWITCH") (pintype "passive"))
    )
    (net (code "160") (name "unconnected-(J9-SWITCH-PadP$2_SWITCH)") (class "Default")
      (node (ref "J9") (pin "P$2_SWITCH") (pinfunction "SWITCH_P$2_SWITCH") (pintype "passive"))
    )
    (net (code "161") (name "unconnected-(J10-SWITCH-PadP$2_SWITCH)") (class "Default")
      (node (ref "J10") (pin "P$2_SWITCH") (pinfunction "SWITCH_P$2_SWITCH") (pintype "passive"))
    )
    (net (code "162") (name "unconnected-(J11-SWITCH-PadP$2_SWITCH)") (class "Default")
      (node (ref "J11") (pin "P$2_SWITCH") (pinfunction "SWITCH_P$2_SWITCH") (pintype "passive"))
    )
    (net (code "163") (name "unconnected-(J12-SWITCH-PadP$2_SWITCH)") (class "Default")
      (node (ref "J12") (pin "P$2_SWITCH") (pinfunction "SWITCH_P$2_SWITCH") (pintype "passive"))
    )
    (net (code "164") (name "unconnected-(J13-SWITCH-PadP$2_SWITCH)") (class "Default")
      (node (ref "J13") (pin "P$2_SWITCH") (pinfunction "SWITCH_P$2_SWITCH") (pintype "passive"))
    )
    (net (code "165") (name "unconnected-(J14-SWITCH-PadP$2_SWITCH)") (class "Default")
      (node (ref "J14") (pin "P$2_SWITCH") (pinfunction "SWITCH_P$2_SWITCH") (pintype "passive"))
    )
    (net (code "166") (name "unconnected-(J15-SWITCH-PadP$2_SWITCH)") (class "Default")
      (node (ref "J15") (pin "P$2_SWITCH") (pinfunction "SWITCH_P$2_SWITCH") (pintype "passive"))
    )
    (net (code "167") (name "unconnected-(J16-SWITCH-PadP$2_SWITCH)") (class "Default")
      (node (ref "J16") (pin "P$2_SWITCH") (pinfunction "SWITCH_P$2_SWITCH") (pintype "passive"))
    )
    (net (code "168") (name "unconnected-(S101-3-PadP1-TB)") (class "Default")
      (node (ref "S101") (pin "P1-TB") (pinfunction "3_P1-TB") (pintype "bidirectional"))
    )
    (net (code "169") (name "unconnected-(SV100-Pad1)") (class "Default")
      (node (ref "SV100") (pin "1") (pinfunction "1_1") (pintype "passive"))
    )
    (net (code "170") (name "unconnected-(SV100-Pad2)") (class "Default")
      (node (ref "SV100") (pin "2") (pinfunction "2_2") (pintype "passive"))
    )
  )
)
